# boardV1-4.net
KiCad netlist of a schematic drawn in EAGLE
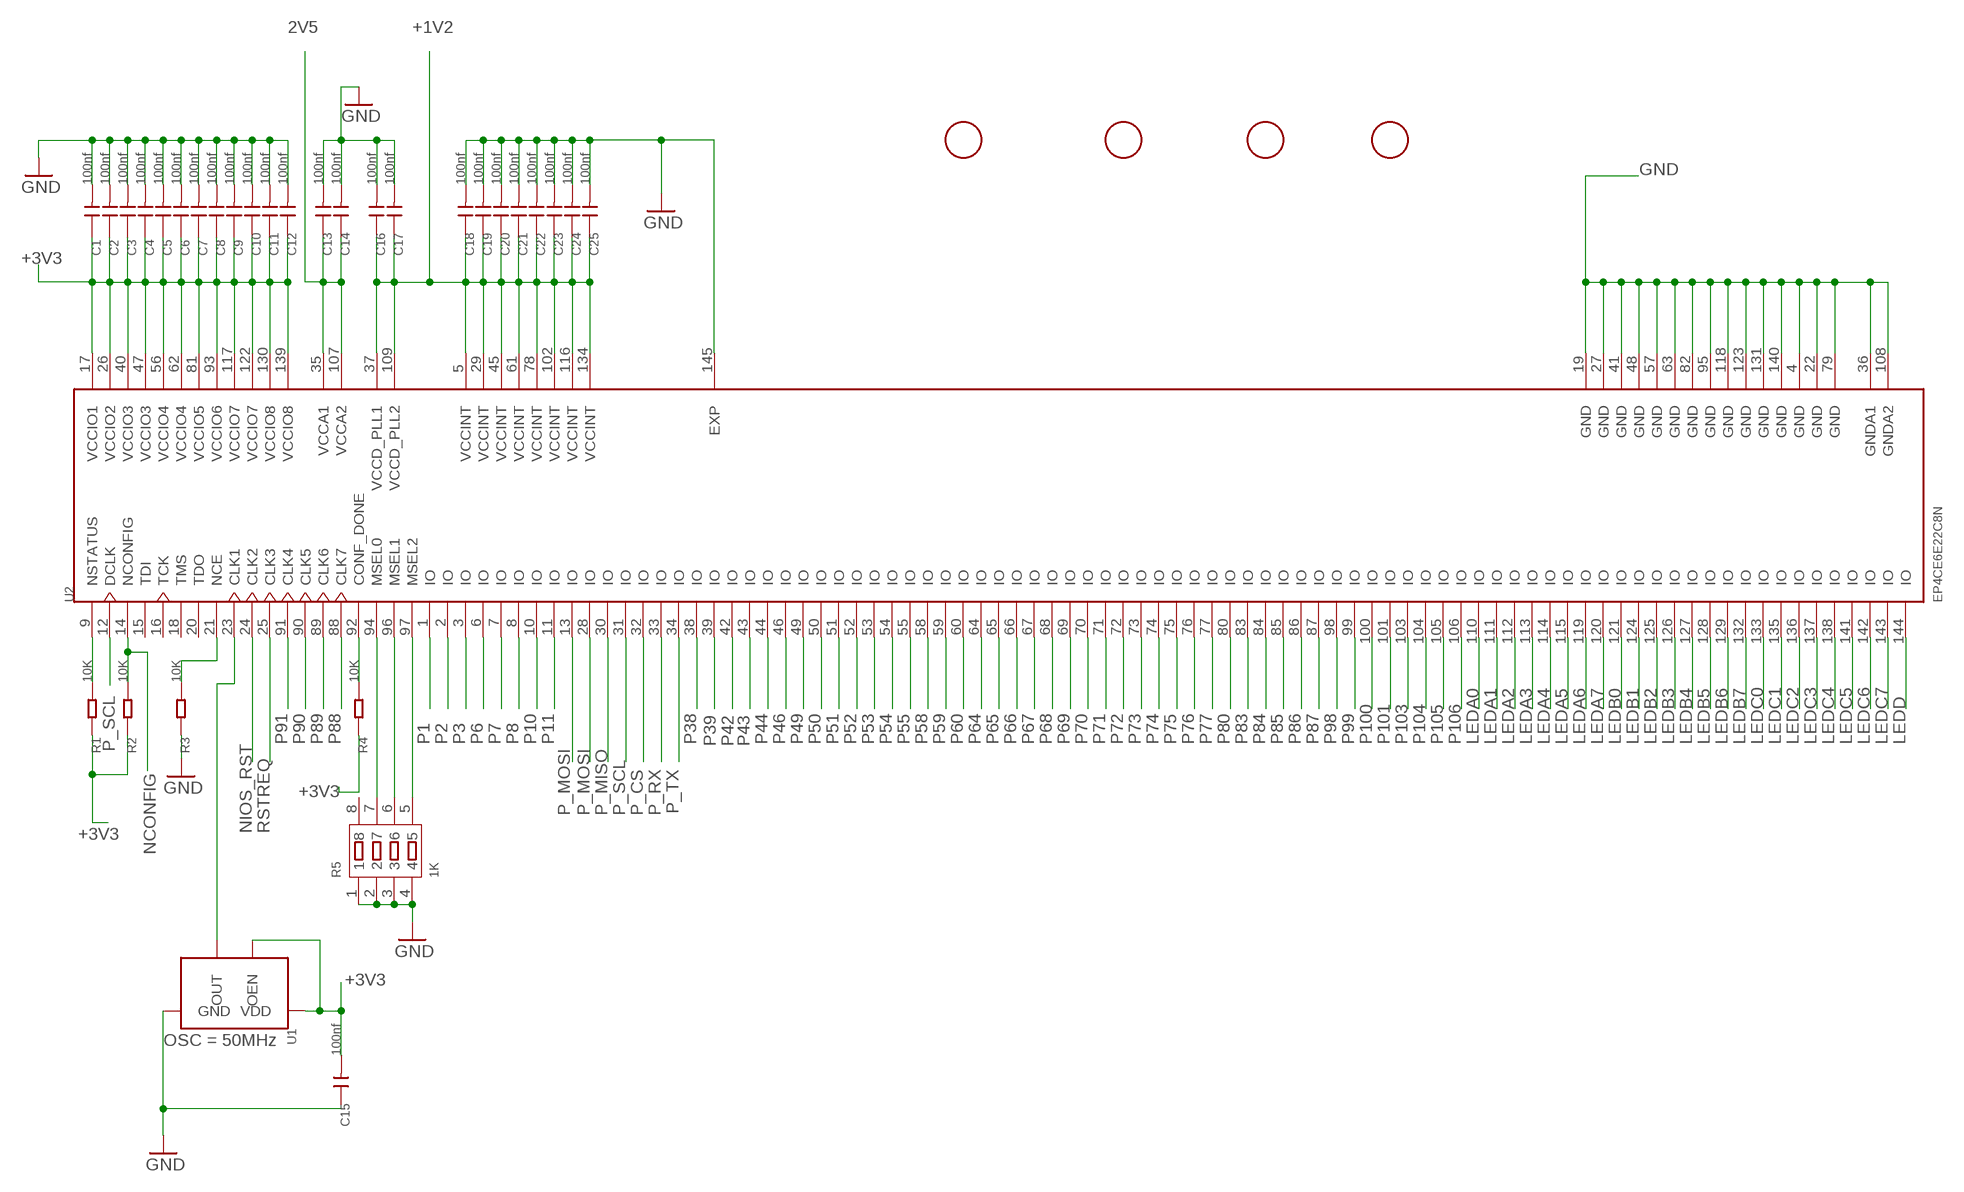
[diagram p0: schematic, sheet 1]
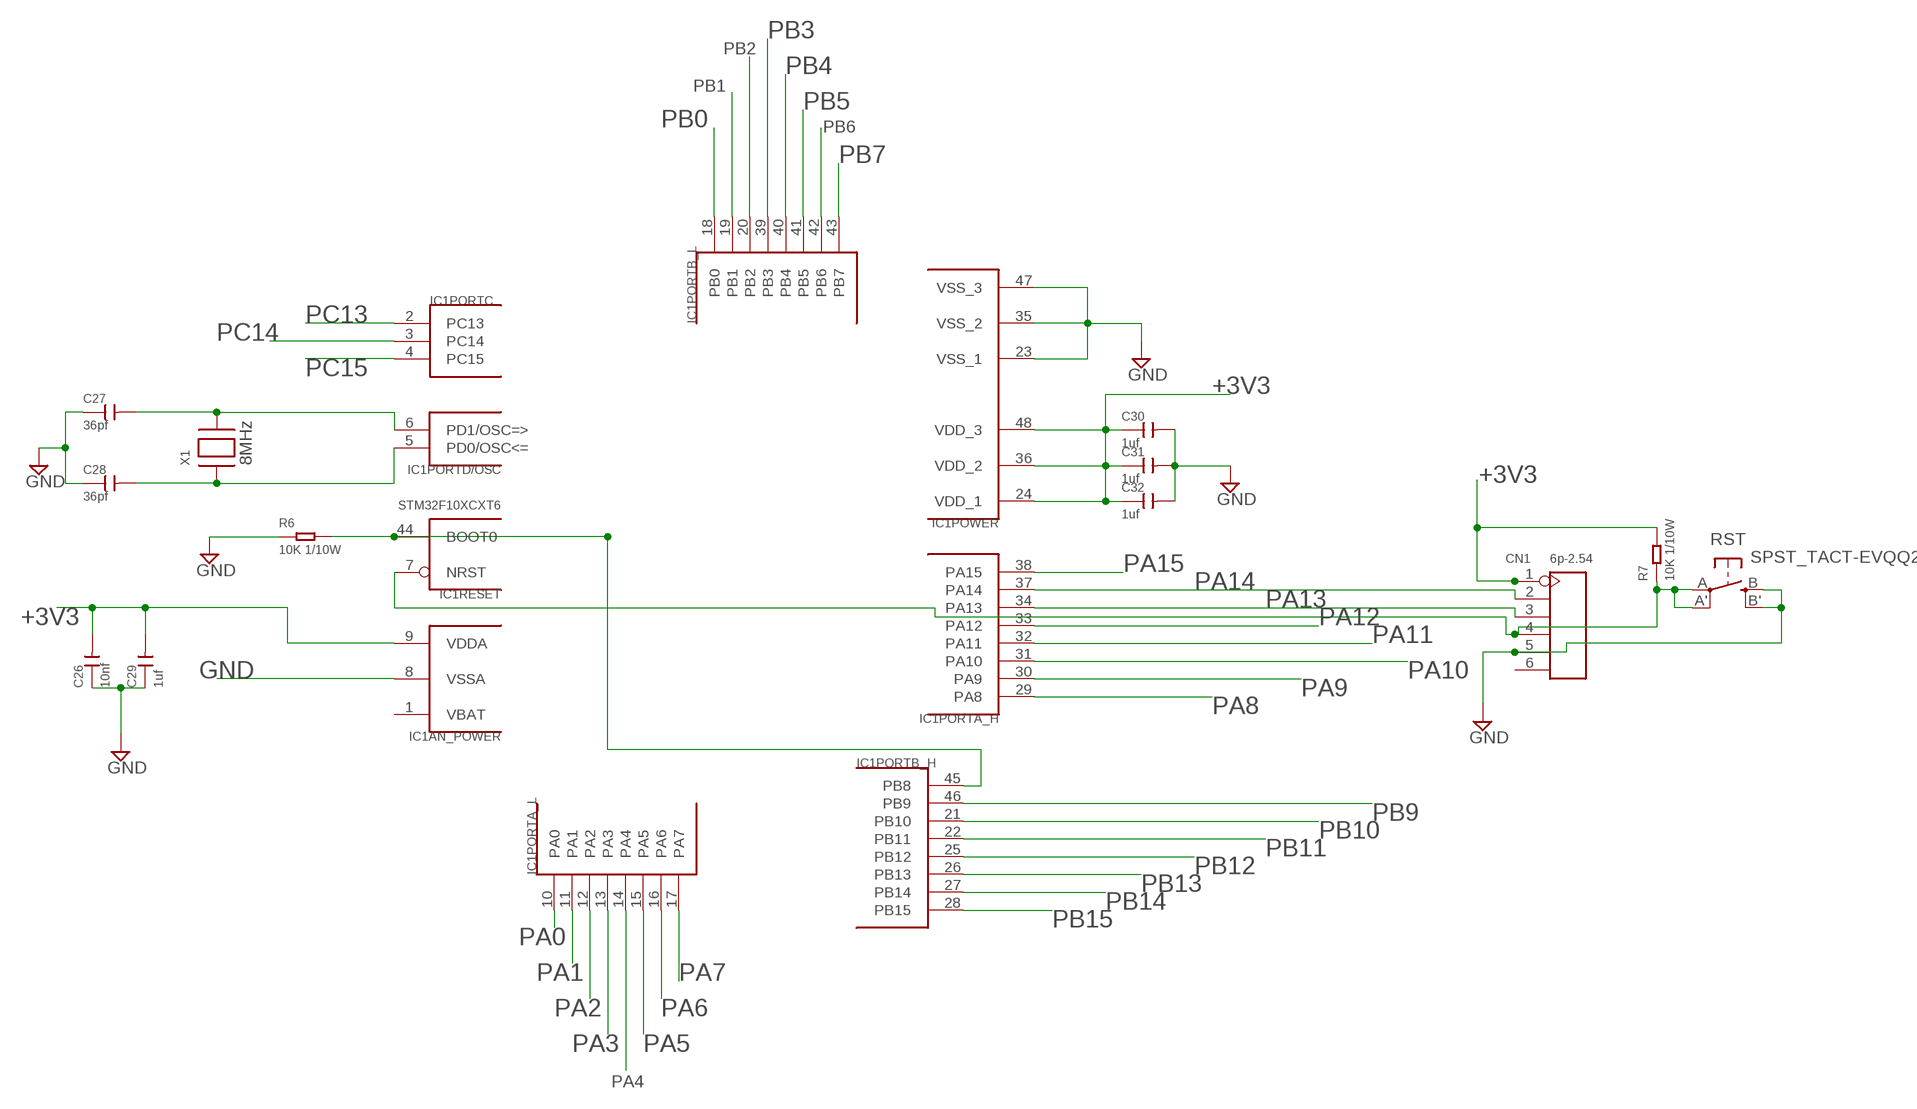
[diagram p1: schematic, sheet 2]
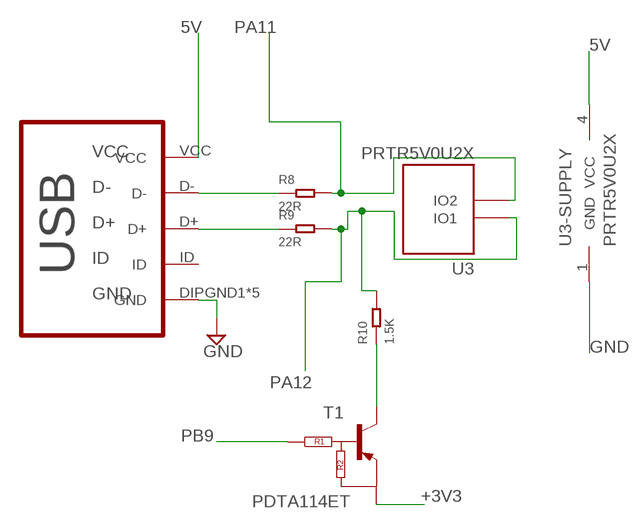
[diagram p2: schematic, sheet 3]
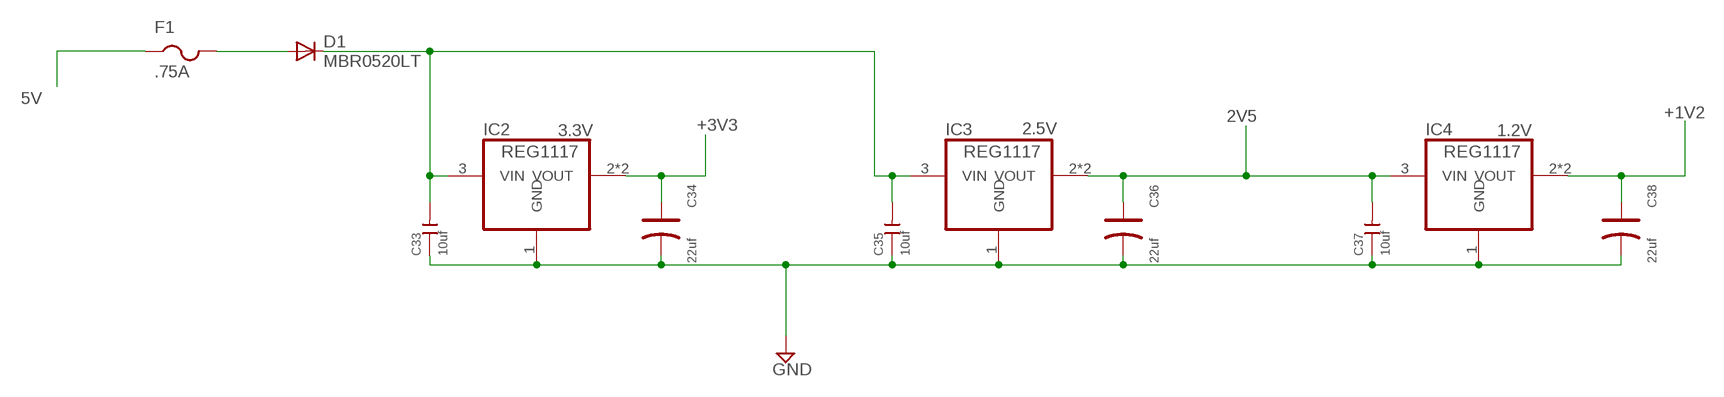
[diagram p3: schematic, sheet 4]
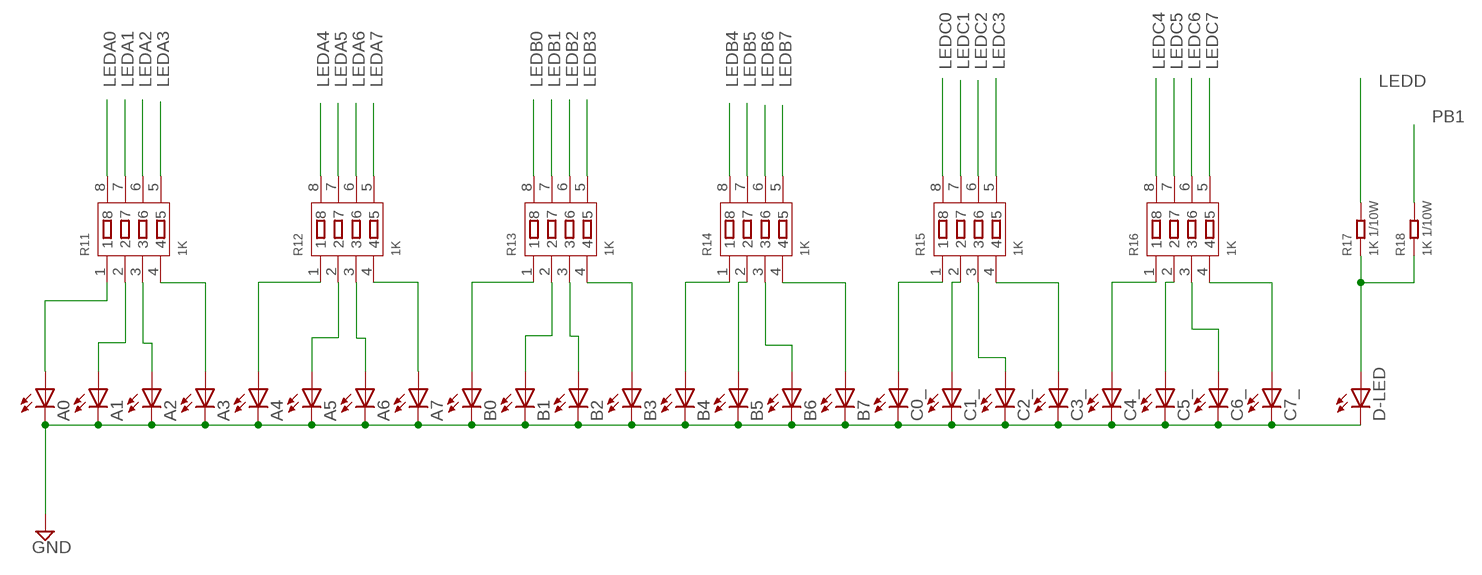
[diagram p4: schematic, sheet 5]
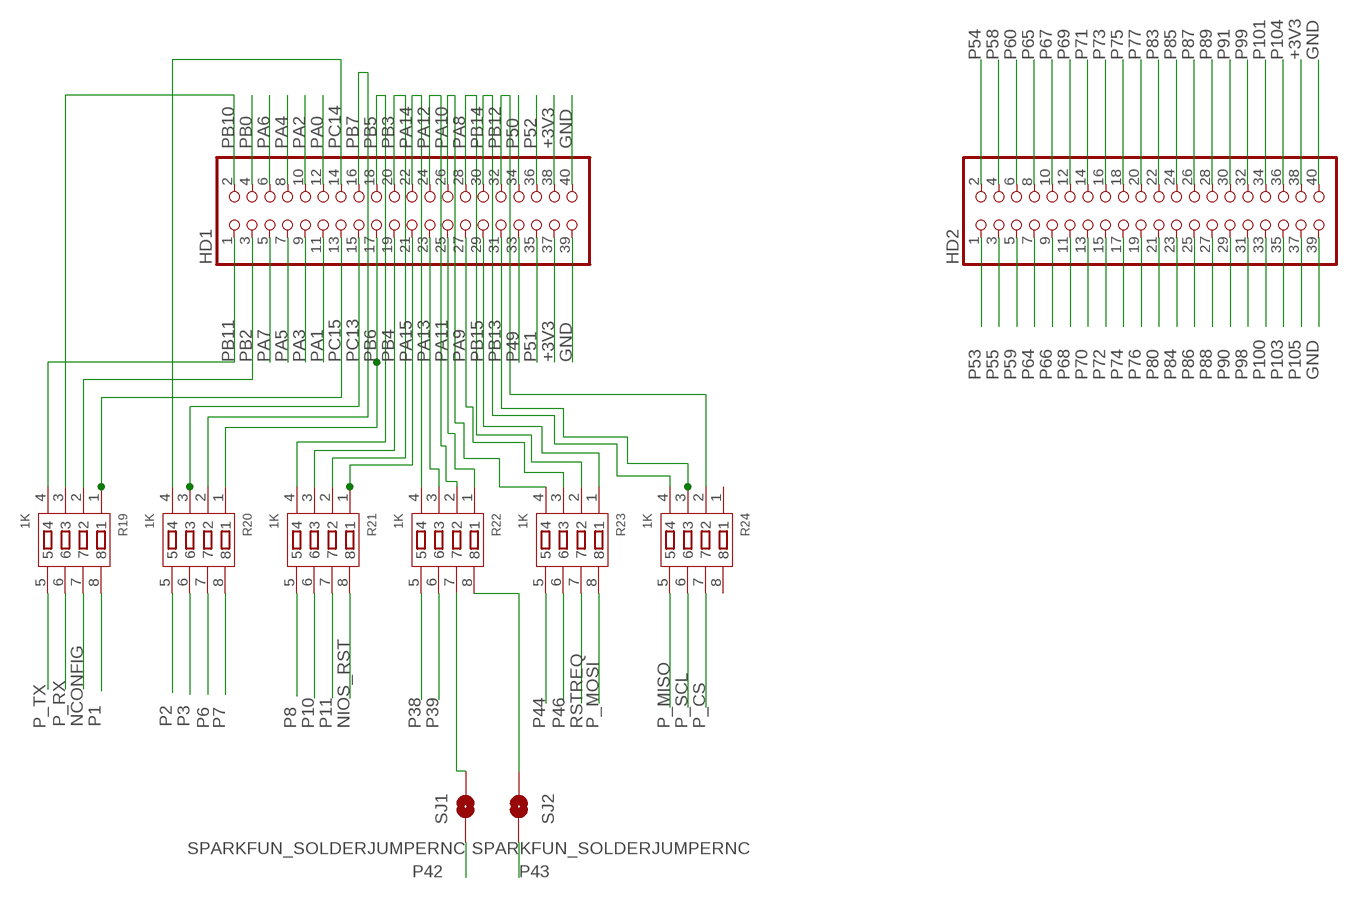
[diagram p5: schematic, sheet 6]
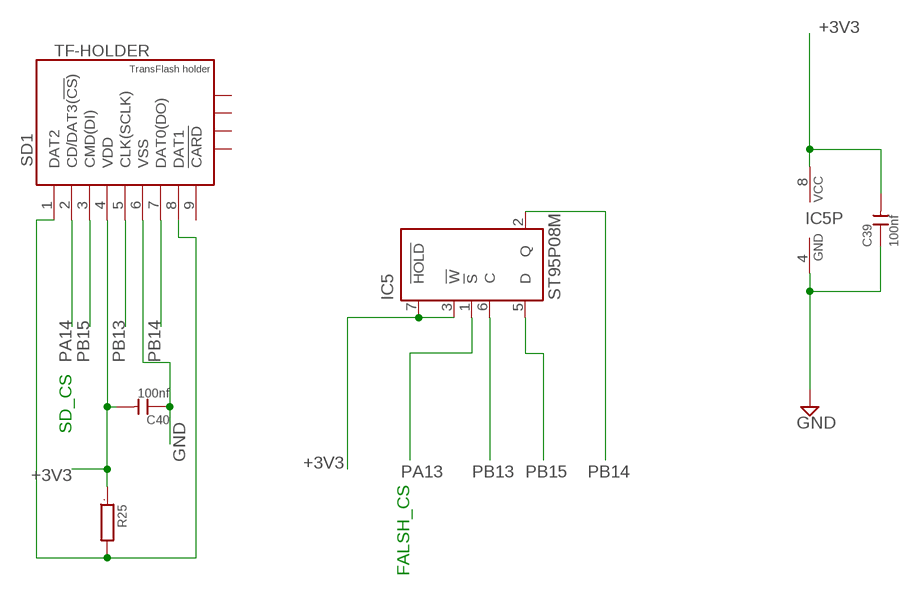
[diagram p6: schematic, sheet 7]

(export (version "E")
  (design (tool "Eeschema 10.0.6"))
  (components
    (comp (ref "HD1")
      (value "PINHD-2X20")
      (footprint "eagle-import:2X20")
      (libsource (lib "eagle-import") (part "PINHD-2X20"))
    )
    (comp (ref "HD2")
      (value "PINHD-2X20")
      (footprint "eagle-import:2X20")
      (libsource (lib "eagle-import") (part "PINHD-2X20"))
    )
    (comp (ref "R19")
      (value "1K")
      (footprint "eagle-import:RA1206-8")
      (fields (field (name "MPN") "Chip-Array-Series-1%"))
      (libsource (lib "eagle-import") (part "Seeed-Resistor_SMD-RES-ARRAY-1K-4R(RA1206-8)"))
    )
    (comp (ref "R20")
      (value "1K")
      (footprint "eagle-import:RA1206-8")
      (fields (field (name "MPN") "Chip-Array-Series-1%"))
      (libsource (lib "eagle-import") (part "Seeed-Resistor_SMD-RES-ARRAY-1K-4R(RA1206-8)"))
    )
    (comp (ref "R21")
      (value "1K")
      (footprint "eagle-import:RA1206-8")
      (fields (field (name "MPN") "Chip-Array-Series-1%"))
      (libsource (lib "eagle-import") (part "Seeed-Resistor_SMD-RES-ARRAY-1K-4R(RA1206-8)"))
    )
    (comp (ref "R22")
      (value "1K")
      (footprint "eagle-import:RA1206-8")
      (fields (field (name "MPN") "Chip-Array-Series-1%"))
      (libsource (lib "eagle-import") (part "Seeed-Resistor_SMD-RES-ARRAY-1K-4R(RA1206-8)"))
    )
    (comp (ref "R23")
      (value "1K")
      (footprint "eagle-import:RA1206-8")
      (fields (field (name "MPN") "Chip-Array-Series-1%"))
      (libsource (lib "eagle-import") (part "Seeed-Resistor_SMD-RES-ARRAY-1K-4R(RA1206-8)"))
    )
    (comp (ref "R24")
      (value "1K")
      (footprint "eagle-import:RA1206-8")
      (fields (field (name "MPN") "Chip-Array-Series-1%"))
      (libsource (lib "eagle-import") (part "Seeed-Resistor_SMD-RES-ARRAY-1K-4R(RA1206-8)"))
    )
    (comp (ref "SJ1")
      (value "SPARKFUN_SOLDERJUMPERNC")
      (footprint "eagle-import:SPARKFUN_SJ_2S")
      (libsource (lib "eagle-import") (part "SPARKFUN_SOLDERJUMPERNC"))
    )
    (comp (ref "SJ2")
      (value "SPARKFUN_SOLDERJUMPERNC")
      (footprint "eagle-import:SPARKFUN_SJ_2S")
      (libsource (lib "eagle-import") (part "SPARKFUN_SOLDERJUMPERNC"))
    )
    (comp (ref "C39")
      (value "100nf")
      (footprint "eagle-import:C0603")
      (fields (field (name "MPN") "CC0603KRX7R9BB104"))
      (libsource (lib "eagle-import") (part "CERAMIC-100NF-50V-10%-X7R(0603)"))
    )
    (comp (ref "C40")
      (value "100nf")
      (footprint "eagle-import:C0603")
      (fields (field (name "MPN") "CC0603KRX7R9BB104"))
      (libsource (lib "eagle-import") (part "CERAMIC-100NF-50V-10%-X7R(0603)"))
    )
    (comp (ref "IC5")
      (value "ST95P08M")
      (footprint "eagle-import:SO08")
      (libsource (lib "eagle-import") (part "ST95P08M"))
    )
    (comp (ref "R25")
      (value "R0603")
      (footprint "eagle-import:0603$1")
      (libsource (lib "eagle-import") (part "R0603"))
    )
    (comp (ref "SD1")
      (value "TF-HOLDER")
      (footprint "eagle-import:TF-PULL")
      (libsource (lib "eagle-import") (part "TF-HOLDER"))
    )
    (comp (ref "C1")
      (value "100nf")
      (footprint "eagle-import:C0603")
      (fields (field (name "MPN") "CC0603KRX7R9BB104"))
      (libsource (lib "eagle-import") (part "Seeed-OPL-Capacitor_CERAMIC-100NF-50V-10%-X7R(0603)"))
    )
    (comp (ref "C2")
      (value "100nf")
      (footprint "eagle-import:C0603")
      (fields (field (name "MPN") "CC0603KRX7R9BB104"))
      (libsource (lib "eagle-import") (part "Seeed-OPL-Capacitor_CERAMIC-100NF-50V-10%-X7R(0603)"))
    )
    (comp (ref "C3")
      (value "100nf")
      (footprint "eagle-import:C0603")
      (fields (field (name "MPN") "CC0603KRX7R9BB104"))
      (libsource (lib "eagle-import") (part "Seeed-OPL-Capacitor_CERAMIC-100NF-50V-10%-X7R(0603)"))
    )
    (comp (ref "C4")
      (value "100nf")
      (footprint "eagle-import:C0603")
      (fields (field (name "MPN") "CC0603KRX7R9BB104"))
      (libsource (lib "eagle-import") (part "Seeed-OPL-Capacitor_CERAMIC-100NF-50V-10%-X7R(0603)"))
    )
    (comp (ref "C5")
      (value "100nf")
      (footprint "eagle-import:C0603")
      (fields (field (name "MPN") "CC0603KRX7R9BB104"))
      (libsource (lib "eagle-import") (part "Seeed-OPL-Capacitor_CERAMIC-100NF-50V-10%-X7R(0603)"))
    )
    (comp (ref "C6")
      (value "100nf")
      (footprint "eagle-import:C0603")
      (fields (field (name "MPN") "CC0603KRX7R9BB104"))
      (libsource (lib "eagle-import") (part "Seeed-OPL-Capacitor_CERAMIC-100NF-50V-10%-X7R(0603)"))
    )
    (comp (ref "C7")
      (value "100nf")
      (footprint "eagle-import:C0603")
      (fields (field (name "MPN") "CC0603KRX7R9BB104"))
      (libsource (lib "eagle-import") (part "Seeed-OPL-Capacitor_CERAMIC-100NF-50V-10%-X7R(0603)"))
    )
    (comp (ref "C8")
      (value "100nf")
      (footprint "eagle-import:C0603")
      (fields (field (name "MPN") "CC0603KRX7R9BB104"))
      (libsource (lib "eagle-import") (part "Seeed-OPL-Capacitor_CERAMIC-100NF-50V-10%-X7R(0603)"))
    )
    (comp (ref "C9")
      (value "100nf")
      (footprint "eagle-import:C0603")
      (fields (field (name "MPN") "CC0603KRX7R9BB104"))
      (libsource (lib "eagle-import") (part "Seeed-OPL-Capacitor_CERAMIC-100NF-50V-10%-X7R(0603)"))
    )
    (comp (ref "C10")
      (value "100nf")
      (footprint "eagle-import:C0603")
      (fields (field (name "MPN") "CC0603KRX7R9BB104"))
      (libsource (lib "eagle-import") (part "Seeed-OPL-Capacitor_CERAMIC-100NF-50V-10%-X7R(0603)"))
    )
    (comp (ref "C11")
      (value "100nf")
      (footprint "eagle-import:C0603")
      (fields (field (name "MPN") "CC0603KRX7R9BB104"))
      (libsource (lib "eagle-import") (part "Seeed-OPL-Capacitor_CERAMIC-100NF-50V-10%-X7R(0603)"))
    )
    (comp (ref "C12")
      (value "100nf")
      (footprint "eagle-import:C0603")
      (fields (field (name "MPN") "CC0603KRX7R9BB104"))
      (libsource (lib "eagle-import") (part "Seeed-OPL-Capacitor_CERAMIC-100NF-50V-10%-X7R(0603)"))
    )
    (comp (ref "C13")
      (value "100nf")
      (footprint "eagle-import:C0603")
      (fields (field (name "MPN") "CC0603KRX7R9BB104"))
      (libsource (lib "eagle-import") (part "Seeed-OPL-Capacitor_CERAMIC-100NF-50V-10%-X7R(0603)"))
    )
    (comp (ref "C14")
      (value "100nf")
      (footprint "eagle-import:C0603")
      (fields (field (name "MPN") "CC0603KRX7R9BB104"))
      (libsource (lib "eagle-import") (part "Seeed-OPL-Capacitor_CERAMIC-100NF-50V-10%-X7R(0603)"))
    )
    (comp (ref "C15")
      (value "100nf")
      (footprint "eagle-import:C0603")
      (fields (field (name "MPN") "CC0603KRX7R9BB104"))
      (libsource (lib "eagle-import") (part "Seeed-OPL-Capacitor_CERAMIC-100NF-50V-10%-X7R(0603)"))
    )
    (comp (ref "C16")
      (value "100nf")
      (footprint "eagle-import:C0603")
      (fields (field (name "MPN") "CC0603KRX7R9BB104"))
      (libsource (lib "eagle-import") (part "Seeed-OPL-Capacitor_CERAMIC-100NF-50V-10%-X7R(0603)"))
    )
    (comp (ref "C17")
      (value "100nf")
      (footprint "eagle-import:C0603")
      (fields (field (name "MPN") "CC0603KRX7R9BB104"))
      (libsource (lib "eagle-import") (part "Seeed-OPL-Capacitor_CERAMIC-100NF-50V-10%-X7R(0603)"))
    )
    (comp (ref "C18")
      (value "100nf")
      (footprint "eagle-import:C0603")
      (fields (field (name "MPN") "CC0603KRX7R9BB104"))
      (libsource (lib "eagle-import") (part "Seeed-OPL-Capacitor_CERAMIC-100NF-50V-10%-X7R(0603)"))
    )
    (comp (ref "C19")
      (value "100nf")
      (footprint "eagle-import:C0603")
      (fields (field (name "MPN") "CC0603KRX7R9BB104"))
      (libsource (lib "eagle-import") (part "Seeed-OPL-Capacitor_CERAMIC-100NF-50V-10%-X7R(0603)"))
    )
    (comp (ref "C20")
      (value "100nf")
      (footprint "eagle-import:C0603")
      (fields (field (name "MPN") "CC0603KRX7R9BB104"))
      (libsource (lib "eagle-import") (part "Seeed-OPL-Capacitor_CERAMIC-100NF-50V-10%-X7R(0603)"))
    )
    (comp (ref "C21")
      (value "100nf")
      (footprint "eagle-import:C0603")
      (fields (field (name "MPN") "CC0603KRX7R9BB104"))
      (libsource (lib "eagle-import") (part "Seeed-OPL-Capacitor_CERAMIC-100NF-50V-10%-X7R(0603)"))
    )
    (comp (ref "C22")
      (value "100nf")
      (footprint "eagle-import:C0603")
      (fields (field (name "MPN") "CC0603KRX7R9BB104"))
      (libsource (lib "eagle-import") (part "Seeed-OPL-Capacitor_CERAMIC-100NF-50V-10%-X7R(0603)"))
    )
    (comp (ref "C23")
      (value "100nf")
      (footprint "eagle-import:C0603")
      (fields (field (name "MPN") "CC0603KRX7R9BB104"))
      (libsource (lib "eagle-import") (part "Seeed-OPL-Capacitor_CERAMIC-100NF-50V-10%-X7R(0603)"))
    )
    (comp (ref "C24")
      (value "100nf")
      (footprint "eagle-import:C0603")
      (fields (field (name "MPN") "CC0603KRX7R9BB104"))
      (libsource (lib "eagle-import") (part "Seeed-OPL-Capacitor_CERAMIC-100NF-50V-10%-X7R(0603)"))
    )
    (comp (ref "C25")
      (value "100nf")
      (footprint "eagle-import:C0603")
      (fields (field (name "MPN") "CC0603KRX7R9BB104"))
      (libsource (lib "eagle-import") (part "Seeed-OPL-Capacitor_CERAMIC-100NF-50V-10%-X7R(0603)"))
    )
    (comp (ref "R1")
      (value "10K")
      (footprint "eagle-import:R0603")
      (fields (field (name "MPN") "RC0603FR-0710KL"))
      (libsource (lib "eagle-import") (part "SMD-RES-10K-1%-1/10W(0603)"))
    )
    (comp (ref "R2")
      (value "10K")
      (footprint "eagle-import:R0603")
      (fields (field (name "MPN") "RC0603FR-0710KL"))
      (libsource (lib "eagle-import") (part "SMD-RES-10K-1%-1/10W(0603)"))
    )
    (comp (ref "R3")
      (value "10K")
      (footprint "eagle-import:R0603")
      (fields (field (name "MPN") "RC0603FR-0710KL"))
      (libsource (lib "eagle-import") (part "SMD-RES-10K-1%-1/10W(0603)"))
    )
    (comp (ref "R4")
      (value "10K")
      (footprint "eagle-import:R0603")
      (fields (field (name "MPN") "RC0603FR-0710KL"))
      (libsource (lib "eagle-import") (part "SMD-RES-10K-1%-1/10W(0603)"))
    )
    (comp (ref "R5")
      (value "1K")
      (footprint "eagle-import:RA1206-8")
      (fields (field (name "MPN") "Chip-Array-Series-1%"))
      (libsource (lib "eagle-import") (part "SMD-RES-ARRAY-1K-4R(RA1206-8)"))
    )
    (comp (ref "U$1")
      (value "FIDUCIAL")
      (footprint "eagle-import:FIDUCIAL_1MM")
      (libsource (lib "eagle-import") (part "FIDUCIAL"))
    )
    (comp (ref "U$2")
      (value "FIDUCIAL")
      (footprint "eagle-import:FIDUCIAL_1MM")
      (libsource (lib "eagle-import") (part "FIDUCIAL"))
    )
    (comp (ref "U$3")
      (value "FIDUCIAL")
      (footprint "eagle-import:FIDUCIAL_1MM")
      (libsource (lib "eagle-import") (part "FIDUCIAL"))
    )
    (comp (ref "U$4")
      (value "FIDUCIAL")
      (footprint "eagle-import:FIDUCIAL_1MM")
      (libsource (lib "eagle-import") (part "FIDUCIAL"))
    )
    (comp (ref "U1")
      (value "306020041_OSC_32.768KHZ-3225_4P")
      (footprint "eagle-import:X3225_4P")
      (fields (field (name "OSC") "50MHz"))
      (libsource (lib "eagle-import") (part "306020041_OSC_32.768KHZ-3225_4P"))
    )
    (comp (ref "U2")
      (value "EP4CE6E22C8N")
      (footprint "eagle-import:QFP50P2200X2200X165-145N")
      (fields (field (name "MF") "Altera"))
      (libsource (lib "eagle-import") (part "EP4CE6E22C8N"))
    )
    (comp (ref "A0")
      (value "LEDCHIPLED_0603")
      (footprint "eagle-import:CHIPLED_0603")
      (libsource (lib "eagle-import") (part "LEDCHIPLED_0603"))
    )
    (comp (ref "A1")
      (value "LEDCHIPLED_0603")
      (footprint "eagle-import:CHIPLED_0603")
      (libsource (lib "eagle-import") (part "LEDCHIPLED_0603"))
    )
    (comp (ref "A2")
      (value "LEDCHIPLED_0603")
      (footprint "eagle-import:CHIPLED_0603")
      (libsource (lib "eagle-import") (part "LEDCHIPLED_0603"))
    )
    (comp (ref "A3")
      (value "LEDCHIPLED_0603")
      (footprint "eagle-import:CHIPLED_0603")
      (libsource (lib "eagle-import") (part "LEDCHIPLED_0603"))
    )
    (comp (ref "A4")
      (value "LEDCHIPLED_0603")
      (footprint "eagle-import:CHIPLED_0603")
      (libsource (lib "eagle-import") (part "LEDCHIPLED_0603"))
    )
    (comp (ref "A5")
      (value "LEDCHIPLED_0603")
      (footprint "eagle-import:CHIPLED_0603")
      (libsource (lib "eagle-import") (part "LEDCHIPLED_0603"))
    )
    (comp (ref "A6")
      (value "LEDCHIPLED_0603")
      (footprint "eagle-import:CHIPLED_0603")
      (libsource (lib "eagle-import") (part "LEDCHIPLED_0603"))
    )
    (comp (ref "A7")
      (value "LEDCHIPLED_0603")
      (footprint "eagle-import:CHIPLED_0603")
      (libsource (lib "eagle-import") (part "LEDCHIPLED_0603"))
    )
    (comp (ref "B0")
      (value "LEDCHIPLED_0603")
      (footprint "eagle-import:CHIPLED_0603")
      (libsource (lib "eagle-import") (part "LEDCHIPLED_0603"))
    )
    (comp (ref "B1")
      (value "LEDCHIPLED_0603")
      (footprint "eagle-import:CHIPLED_0603")
      (libsource (lib "eagle-import") (part "LEDCHIPLED_0603"))
    )
    (comp (ref "B2")
      (value "LEDCHIPLED_0603")
      (footprint "eagle-import:CHIPLED_0603")
      (libsource (lib "eagle-import") (part "LEDCHIPLED_0603"))
    )
    (comp (ref "B3")
      (value "LEDCHIPLED_0603")
      (footprint "eagle-import:CHIPLED_0603")
      (libsource (lib "eagle-import") (part "LEDCHIPLED_0603"))
    )
    (comp (ref "B4")
      (value "LEDCHIPLED_0603")
      (footprint "eagle-import:CHIPLED_0603")
      (libsource (lib "eagle-import") (part "LEDCHIPLED_0603"))
    )
    (comp (ref "B5")
      (value "LEDCHIPLED_0603")
      (footprint "eagle-import:CHIPLED_0603")
      (libsource (lib "eagle-import") (part "LEDCHIPLED_0603"))
    )
    (comp (ref "B6")
      (value "LEDCHIPLED_0603")
      (footprint "eagle-import:CHIPLED_0603")
      (libsource (lib "eagle-import") (part "LEDCHIPLED_0603"))
    )
    (comp (ref "B7")
      (value "LEDCHIPLED_0603")
      (footprint "eagle-import:CHIPLED_0603")
      (libsource (lib "eagle-import") (part "LEDCHIPLED_0603"))
    )
    (comp (ref "C0_")
      (value "LEDCHIPLED_0603")
      (footprint "eagle-import:CHIPLED_0603")
      (libsource (lib "eagle-import") (part "LEDCHIPLED_0603"))
    )
    (comp (ref "C1_")
      (value "LEDCHIPLED_0603")
      (footprint "eagle-import:CHIPLED_0603")
      (libsource (lib "eagle-import") (part "LEDCHIPLED_0603"))
    )
    (comp (ref "C2_")
      (value "LEDCHIPLED_0603")
      (footprint "eagle-import:CHIPLED_0603")
      (libsource (lib "eagle-import") (part "LEDCHIPLED_0603"))
    )
    (comp (ref "C3_")
      (value "LEDCHIPLED_0603")
      (footprint "eagle-import:CHIPLED_0603")
      (libsource (lib "eagle-import") (part "LEDCHIPLED_0603"))
    )
    (comp (ref "C4_")
      (value "LEDCHIPLED_0603")
      (footprint "eagle-import:CHIPLED_0603")
      (libsource (lib "eagle-import") (part "LEDCHIPLED_0603"))
    )
    (comp (ref "C5_")
      (value "LEDCHIPLED_0603")
      (footprint "eagle-import:CHIPLED_0603")
      (libsource (lib "eagle-import") (part "LEDCHIPLED_0603"))
    )
    (comp (ref "C6_")
      (value "LEDCHIPLED_0603")
      (footprint "eagle-import:CHIPLED_0603")
      (libsource (lib "eagle-import") (part "LEDCHIPLED_0603"))
    )
    (comp (ref "C7_")
      (value "LEDCHIPLED_0603")
      (footprint "eagle-import:CHIPLED_0603")
      (libsource (lib "eagle-import") (part "LEDCHIPLED_0603"))
    )
    (comp (ref "D-LED")
      (value "LEDCHIPLED_0603")
      (footprint "eagle-import:CHIPLED_0603")
      (libsource (lib "eagle-import") (part "LEDCHIPLED_0603"))
    )
    (comp (ref "R11")
      (value "1K")
      (footprint "eagle-import:RA1206-8")
      (fields (field (name "MPN") "Chip-Array-Series-1%"))
      (libsource (lib "eagle-import") (part "SMD-RES-ARRAY-1K-4R(RA1206-8)"))
    )
    (comp (ref "R12")
      (value "1K")
      (footprint "eagle-import:RA1206-8")
      (fields (field (name "MPN") "Chip-Array-Series-1%"))
      (libsource (lib "eagle-import") (part "SMD-RES-ARRAY-1K-4R(RA1206-8)"))
    )
    (comp (ref "R13")
      (value "1K")
      (footprint "eagle-import:RA1206-8")
      (fields (field (name "MPN") "Chip-Array-Series-1%"))
      (libsource (lib "eagle-import") (part "SMD-RES-ARRAY-1K-4R(RA1206-8)"))
    )
    (comp (ref "R14")
      (value "1K")
      (footprint "eagle-import:RA1206-8")
      (fields (field (name "MPN") "Chip-Array-Series-1%"))
      (libsource (lib "eagle-import") (part "SMD-RES-ARRAY-1K-4R(RA1206-8)"))
    )
    (comp (ref "R15")
      (value "1K")
      (footprint "eagle-import:RA1206-8")
      (fields (field (name "MPN") "Chip-Array-Series-1%"))
      (libsource (lib "eagle-import") (part "SMD-RES-ARRAY-1K-4R(RA1206-8)"))
    )
    (comp (ref "R16")
      (value "1K")
      (footprint "eagle-import:RA1206-8")
      (fields (field (name "MPN") "Chip-Array-Series-1%"))
      (libsource (lib "eagle-import") (part "SMD-RES-ARRAY-1K-4R(RA1206-8)"))
    )
    (comp (ref "R17")
      (value "1K 1/10W")
      (footprint "eagle-import:R0603")
      (fields (field (name "MPN") "RC0603JR-071KL"))
      (libsource (lib "eagle-import") (part "SMD-RES-1K-5%-1/10W(0603)"))
    )
    (comp (ref "R18")
      (value "1K 1/10W")
      (footprint "eagle-import:R0603")
      (fields (field (name "MPN") "RC0603JR-071KL"))
      (libsource (lib "eagle-import") (part "SMD-RES-1K-5%-1/10W(0603)"))
    )
    (comp (ref "C33")
      (value "10uf")
      (footprint "eagle-import:C0805")
      (fields (field (name "MPN") "CC0805KKX5R8BB106"))
      (libsource (lib "eagle-import") (part "CERAMIC-10UF-25V-10%-X5R(0805)"))
    )
    (comp (ref "C34")
      (value "22uf")
      (footprint "eagle-import:AVX-A")
      (fields (field (name "MPN") "TAJA226K006RNJ"))
      (libsource (lib "eagle-import") (part "TANTALUM-SMD-22UF-6.3V(AVX-A)"))
    )
    (comp (ref "C35")
      (value "10uf")
      (footprint "eagle-import:C0805")
      (fields (field (name "MPN") "CC0805KKX5R8BB106"))
      (libsource (lib "eagle-import") (part "CERAMIC-10UF-25V-10%-X5R(0805)"))
    )
    (comp (ref "C36")
      (value "22uf")
      (footprint "eagle-import:AVX-A")
      (fields (field (name "MPN") "TAJA226K006RNJ"))
      (libsource (lib "eagle-import") (part "TANTALUM-SMD-22UF-6.3V(AVX-A)"))
    )
    (comp (ref "C37")
      (value "10uf")
      (footprint "eagle-import:C0805")
      (fields (field (name "MPN") "CC0805KKX5R8BB106"))
      (libsource (lib "eagle-import") (part "CERAMIC-10UF-25V-10%-X5R(0805)"))
    )
    (comp (ref "C38")
      (value "22uf")
      (footprint "eagle-import:AVX-A")
      (fields (field (name "MPN") "TAJA226K006RNJ"))
      (libsource (lib "eagle-import") (part "TANTALUM-SMD-22UF-6.3V(AVX-A)"))
    )
    (comp (ref "D1")
      (value "MBR0520LT")
      (footprint "eagle-import:SOD123")
      (libsource (lib "eagle-import") (part "MBR0520LT"))
    )
    (comp (ref "F1")
      (value ".75A")
      (footprint "eagle-import:R1206")
      (libsource (lib "eagle-import") (part "PTCFUSE-1206"))
    )
    (comp (ref "IC2")
      (value "REG1117")
      (footprint "eagle-import:SOT223")
      (fields (field (name "OUT") "3.3V"))
      (libsource (lib "eagle-import") (part "REG1117"))
    )
    (comp (ref "IC3")
      (value "REG1117")
      (footprint "eagle-import:SOT223")
      (fields (field (name "OUT") "2.5V"))
      (libsource (lib "eagle-import") (part "REG1117"))
    )
    (comp (ref "IC4")
      (value "REG1117")
      (footprint "eagle-import:SOT223")
      (fields (field (name "V") "1.2V"))
      (libsource (lib "eagle-import") (part "REG1117"))
    )
    (comp (ref "C26")
      (value "10nf")
      (footprint "eagle-import:C0603")
      (fields (field (name "MPN") "CC0603KRX7R9BB103"))
      (libsource (lib "eagle-import") (part "CERAMIC-10NF-50V-10%-X7R(0603)"))
    )
    (comp (ref "C27")
      (value "36pf")
      (footprint "eagle-import:C0603")
      (fields (field (name "MPN") "CC0603JRNPO9BN120"))
      (libsource (lib "eagle-import") (part "CERAMIC-12PF-50V-5%-NPO(0603)"))
    )
    (comp (ref "C28")
      (value "36pf")
      (footprint "eagle-import:C0603")
      (fields (field (name "MPN") "CC0603JRNPO9BN120"))
      (libsource (lib "eagle-import") (part "CERAMIC-12PF-50V-5%-NPO(0603)"))
    )
    (comp (ref "C29")
      (value "1uf")
      (footprint "eagle-import:C0603")
      (fields (field (name "MPN") "CC0603KRX7R8BB105"))
      (libsource (lib "eagle-import") (part "CERAMIC-1UF-25V-10%-X7R(0603)"))
    )
    (comp (ref "C30")
      (value "1uf")
      (footprint "eagle-import:C0603")
      (fields (field (name "MPN") "CC0603KRX7R8BB105"))
      (libsource (lib "eagle-import") (part "CERAMIC-1UF-25V-10%-X7R(0603)"))
    )
    (comp (ref "C31")
      (value "1uf")
      (footprint "eagle-import:C0603")
      (fields (field (name "MPN") "CC0603KRX7R8BB105"))
      (libsource (lib "eagle-import") (part "CERAMIC-1UF-25V-10%-X7R(0603)"))
    )
    (comp (ref "C32")
      (value "1uf")
      (footprint "eagle-import:C0603")
      (fields (field (name "MPN") "CC0603KRX7R8BB105"))
      (libsource (lib "eagle-import") (part "CERAMIC-1UF-25V-10%-X7R(0603)"))
    )
    (comp (ref "CN1")
      (value "6p-2.54")
      (footprint "eagle-import:H6-2.54")
      (fields (field (name "MPN") "F185-1106A1BSYC1"))
      (libsource (lib "eagle-import") (part "DIP-BLACK-FEMALE-HEADER-VERT(6P-2.54)"))
    )
    (comp (ref "IC1")
      (value "STM32F10XCXT6")
      (footprint "eagle-import:TQFP48")
      (libsource (lib "eagle-import") (part "STM32F10XCXT6"))
    )
    (comp (ref "R6")
      (value "10K 1/10W")
      (footprint "eagle-import:R0603")
      (fields (field (name "MPN") "RC0603JR-0710KL"))
      (libsource (lib "eagle-import") (part "SMD-RES-10K-5%-1/10W(0603)"))
    )
    (comp (ref "R7")
      (value "10K 1/10W")
      (footprint "eagle-import:R0603")
      (fields (field (name "MPN") "RC0603JR-0710KL"))
      (libsource (lib "eagle-import") (part "SMD-RES-10K-5%-1/10W(0603)"))
    )
    (comp (ref "RST")
      (value "SPST_TACT-EVQQ2")
      (footprint "eagle-import:EVQ-Q2")
      (libsource (lib "eagle-import") (part "SPST_TACT-EVQQ2"))
    )
    (comp (ref "X1")
      (value "306010047_XTAL_12MHZ-5032_2P")
      (footprint "eagle-import:X5032_2P")
      (fields (field (name "FQ") "8MHz"))
      (libsource (lib "eagle-import") (part "306010047_XTAL_12MHZ-5032_2P"))
    )
    (comp (ref "R8")
      (value "22R")
      (footprint "eagle-import:R0603")
      (fields (field (name "MPN") "RC0603JR-0722RL"))
      (libsource (lib "eagle-import") (part "SMD-RES-22R-5%-1/10W(0603)"))
    )
    (comp (ref "R9")
      (value "22R")
      (footprint "eagle-import:R0603")
      (fields (field (name "MPN") "RC0603JR-0722RL"))
      (libsource (lib "eagle-import") (part "SMD-RES-22R-5%-1/10W(0603)"))
    )
    (comp (ref "R10")
      (value "1.5K")
      (footprint "eagle-import:R0603")
      (fields (field (name "MPN") "RC0603FR-071K5L"))
      (libsource (lib "eagle-import") (part "SMD-RES-1.5K-1%-1/10W(0603)"))
    )
    (comp (ref "T1")
      (value "PDTA114ET")
      (footprint "eagle-import:SOT23")
      (libsource (lib "eagle-import") (part "PDTA114TE"))
    )
    (comp (ref "U3")
      (value "PRTR5V0U2X")
      (footprint "eagle-import:SOT-143B")
      (fields
        (field (name "MANUFACTURER") "NXP Semiconductors")
        (field (name "PART_NUMBER") "PRTR5V0U2X,215")
      )
      (libsource (lib "eagle-import") (part "PRTR5V0U2X?"))
    )
    (comp (ref "USB")
      (value "MICRO-USB-B")
      (footprint "eagle-import:MICRO_USB_4_LEGS")
      (libsource (lib "eagle-import") (part "MICRO-USB-B"))
    )
  )
  (nets
    (net (code "1") (name "+1V2") (class "Default")
      (node (ref "C16") (pin "1") (pinfunction "1_1") (pintype "passive"))
      (node (ref "C17") (pin "1") (pinfunction "1_1") (pintype "passive"))
      (node (ref "C18") (pin "1") (pinfunction "1_1") (pintype "passive"))
      (node (ref "C19") (pin "1") (pinfunction "1_1") (pintype "passive"))
      (node (ref "C20") (pin "1") (pinfunction "1_1") (pintype "passive"))
      (node (ref "C21") (pin "1") (pinfunction "1_1") (pintype "passive"))
      (node (ref "C22") (pin "1") (pinfunction "1_1") (pintype "passive"))
      (node (ref "C23") (pin "1") (pinfunction "1_1") (pintype "passive"))
      (node (ref "C24") (pin "1") (pinfunction "1_1") (pintype "passive"))
      (node (ref "C25") (pin "1") (pinfunction "1_1") (pintype "passive"))
      (node (ref "C38") (pin "+") (pinfunction "+_+") (pintype "passive"))
      (node (ref "IC4") (pin "2") (pinfunction "VOUT_2") (pintype "output"))
      (node (ref "IC4") (pin "4") (pinfunction "VOUT_4") (pintype "output"))
      (node (ref "U2") (pin "102") (pinfunction "VCCINT_102") (pintype "power_in"))
      (node (ref "U2") (pin "109") (pinfunction "VCCD_PLL2_109") (pintype "power_in"))
      (node (ref "U2") (pin "116") (pinfunction "VCCINT_116") (pintype "power_in"))
      (node (ref "U2") (pin "134") (pinfunction "VCCINT_134") (pintype "power_in"))
      (node (ref "U2") (pin "29") (pinfunction "VCCINT_29") (pintype "power_in"))
      (node (ref "U2") (pin "37") (pinfunction "VCCD_PLL1_37") (pintype "power_in"))
      (node (ref "U2") (pin "45") (pinfunction "VCCINT_45") (pintype "power_in"))
      (node (ref "U2") (pin "5") (pinfunction "VCCINT_5") (pintype "power_in"))
      (node (ref "U2") (pin "61") (pinfunction "VCCINT_61") (pintype "power_in"))
      (node (ref "U2") (pin "78") (pinfunction "VCCINT_78") (pintype "power_in"))
    )
    (net (code "2") (name "+3V3") (class "Default")
      (node (ref "C1") (pin "1") (pinfunction "1_1") (pintype "passive"))
      (node (ref "C10") (pin "1") (pinfunction "1_1") (pintype "passive"))
      (node (ref "C11") (pin "1") (pinfunction "1_1") (pintype "passive"))
      (node (ref "C12") (pin "1") (pinfunction "1_1") (pintype "passive"))
      (node (ref "C15") (pin "2") (pinfunction "2_2") (pintype "passive"))
      (node (ref "C2") (pin "1") (pinfunction "1_1") (pintype "passive"))
      (node (ref "C26") (pin "2") (pinfunction "2_2") (pintype "passive"))
      (node (ref "C29") (pin "2") (pinfunction "2_2") (pintype "passive"))
      (node (ref "C3") (pin "1") (pinfunction "1_1") (pintype "passive"))
      (node (ref "C30") (pin "1") (pinfunction "1_1") (pintype "passive"))
      (node (ref "C31") (pin "1") (pinfunction "1_1") (pintype "passive"))
      (node (ref "C32") (pin "1") (pinfunction "1_1") (pintype "passive"))
      (node (ref "C34") (pin "+") (pinfunction "+_+") (pintype "passive"))
      (node (ref "C39") (pin "2") (pinfunction "2_2") (pintype "passive"))
      (node (ref "C4") (pin "1") (pinfunction "1_1") (pintype "passive"))
      (node (ref "C40") (pin "2") (pinfunction "2_2") (pintype "passive"))
      (node (ref "C5") (pin "1") (pinfunction "1_1") (pintype "passive"))
      (node (ref "C6") (pin "1") (pinfunction "1_1") (pintype "passive"))
      (node (ref "C7") (pin "1") (pinfunction "1_1") (pintype "passive"))
      (node (ref "C8") (pin "1") (pinfunction "1_1") (pintype "passive"))
      (node (ref "C9") (pin "1") (pinfunction "1_1") (pintype "passive"))
      (node (ref "CN1") (pin "1") (pinfunction "1_1") (pintype "bidirectional"))
      (node (ref "HD1") (pin "37") (pinfunction "37_37") (pintype "passive"))
      (node (ref "HD1") (pin "38") (pinfunction "38_38") (pintype "passive"))
      (node (ref "HD2") (pin "38") (pinfunction "38_38") (pintype "passive"))
      (node (ref "IC1") (pin "24") (pinfunction "VDD_1_24") (pintype "power_in"))
      (node (ref "IC1") (pin "36") (pinfunction "VDD_2_36") (pintype "power_in"))
      (node (ref "IC1") (pin "48") (pinfunction "VDD_3_48") (pintype "power_in"))
      (node (ref "IC1") (pin "9") (pinfunction "VDDA_9") (pintype "power_in"))
      (node (ref "IC2") (pin "2") (pinfunction "VOUT_2") (pintype "output"))
      (node (ref "IC2") (pin "4") (pinfunction "VOUT_4") (pintype "output"))
      (node (ref "IC5") (pin "3") (pinfunction "~{W}_3") (pintype "input"))
      (node (ref "IC5") (pin "7") (pinfunction "~{HOLD}_7") (pintype "input"))
      (node (ref "IC5") (pin "8") (pinfunction "VCC_8") (pintype "power_in"))
      (node (ref "R1") (pin "1") (pinfunction "1_1") (pintype "passive"))
      (node (ref "R2") (pin "1") (pinfunction "1_1") (pintype "passive"))
      (node (ref "R25") (pin "1") (pinfunction "1_1") (pintype "passive"))
      (node (ref "R4") (pin "1") (pinfunction "1_1") (pintype "passive"))
      (node (ref "R7") (pin "2") (pinfunction "2_2") (pintype "passive"))
      (node (ref "SD1") (pin "4") (pinfunction "VDD_4") (pintype "power_in"))
      (node (ref "T1") (pin "2") (pinfunction "E_2") (pintype "passive"))
      (node (ref "U1") (pin "P$1") (pinfunction "OEN_P$1") (pintype "bidirectional"))
      (node (ref "U1") (pin "P$4") (pinfunction "VDD_P$4") (pintype "power_in"))
      (node (ref "U2") (pin "117") (pinfunction "VCCIO7_117") (pintype "power_in"))
      (node (ref "U2") (pin "122") (pinfunction "VCCIO7_122") (pintype "power_in"))
      (node (ref "U2") (pin "130") (pinfunction "VCCIO8_130") (pintype "power_in"))
      (node (ref "U2") (pin "139") (pinfunction "VCCIO8_139") (pintype "power_in"))
      (node (ref "U2") (pin "17") (pinfunction "VCCIO1_17") (pintype "power_in"))
      (node (ref "U2") (pin "26") (pinfunction "VCCIO2_26") (pintype "power_in"))
      (node (ref "U2") (pin "40") (pinfunction "VCCIO3_40") (pintype "power_in"))
      (node (ref "U2") (pin "47") (pinfunction "VCCIO3_47") (pintype "power_in"))
      (node (ref "U2") (pin "56") (pinfunction "VCCIO4_56") (pintype "power_in"))
      (node (ref "U2") (pin "62") (pinfunction "VCCIO4_62") (pintype "power_in"))
      (node (ref "U2") (pin "81") (pinfunction "VCCIO5_81") (pintype "power_in"))
      (node (ref "U2") (pin "93") (pinfunction "VCCIO6_93") (pintype "power_in"))
    )
    (net (code "3") (name "2V5") (class "Default")
      (node (ref "C13") (pin "1") (pinfunction "1_1") (pintype "passive"))
      (node (ref "C14") (pin "1") (pinfunction "1_1") (pintype "passive"))
      (node (ref "C36") (pin "+") (pinfunction "+_+") (pintype "passive"))
      (node (ref "C37") (pin "2") (pinfunction "2_2") (pintype "passive"))
      (node (ref "IC3") (pin "2") (pinfunction "VOUT_2") (pintype "output"))
      (node (ref "IC3") (pin "4") (pinfunction "VOUT_4") (pintype "output"))
      (node (ref "IC4") (pin "3") (pinfunction "VIN_3") (pintype "input"))
      (node (ref "U2") (pin "107") (pinfunction "VCCA2_107") (pintype "power_in"))
      (node (ref "U2") (pin "35") (pinfunction "VCCA1_35") (pintype "power_in"))
    )
    (net (code "4") (name "5V") (class "Default")
      (node (ref "F1") (pin "1") (pinfunction "1_1") (pintype "passive"))
      (node (ref "U3") (pin "4") (pinfunction "VCC_4") (pintype "bidirectional"))
      (node (ref "USB") (pin "VCC") (pinfunction "VCC_VCC") (pintype "bidirectional"))
    )
    (net (code "5") (name "GND") (class "Default")
      (node (ref "A0") (pin "C") (pinfunction "C_C") (pintype "passive"))
      (node (ref "A1") (pin "C") (pinfunction "C_C") (pintype "passive"))
      (node (ref "A2") (pin "C") (pinfunction "C_C") (pintype "passive"))
      (node (ref "A3") (pin "C") (pinfunction "C_C") (pintype "passive"))
      (node (ref "A4") (pin "C") (pinfunction "C_C") (pintype "passive"))
      (node (ref "A5") (pin "C") (pinfunction "C_C") (pintype "passive"))
      (node (ref "A6") (pin "C") (pinfunction "C_C") (pintype "passive"))
      (node (ref "A7") (pin "C") (pinfunction "C_C") (pintype "passive"))
      (node (ref "B0") (pin "C") (pinfunction "C_C") (pintype "passive"))
      (node (ref "B1") (pin "C") (pinfunction "C_C") (pintype "passive"))
      (node (ref "B2") (pin "C") (pinfunction "C_C") (pintype "passive"))
      (node (ref "B3") (pin "C") (pinfunction "C_C") (pintype "passive"))
      (node (ref "B4") (pin "C") (pinfunction "C_C") (pintype "passive"))
      (node (ref "B5") (pin "C") (pinfunction "C_C") (pintype "passive"))
      (node (ref "B6") (pin "C") (pinfunction "C_C") (pintype "passive"))
      (node (ref "B7") (pin "C") (pinfunction "C_C") (pintype "passive"))
      (node (ref "C0_") (pin "C") (pinfunction "C_C") (pintype "passive"))
      (node (ref "C1") (pin "2") (pinfunction "2_2") (pintype "passive"))
      (node (ref "C10") (pin "2") (pinfunction "2_2") (pintype "passive"))
      (node (ref "C11") (pin "2") (pinfunction "2_2") (pintype "passive"))
      (node (ref "C12") (pin "2") (pinfunction "2_2") (pintype "passive"))
      (node (ref "C13") (pin "2") (pinfunction "2_2") (pintype "passive"))
      (node (ref "C14") (pin "2") (pinfunction "2_2") (pintype "passive"))
      (node (ref "C15") (pin "1") (pinfunction "1_1") (pintype "passive"))
      (node (ref "C16") (pin "2") (pinfunction "2_2") (pintype "passive"))
      (node (ref "C17") (pin "2") (pinfunction "2_2") (pintype "passive"))
      (node (ref "C18") (pin "2") (pinfunction "2_2") (pintype "passive"))
      (node (ref "C19") (pin "2") (pinfunction "2_2") (pintype "passive"))
      (node (ref "C1_") (pin "C") (pinfunction "C_C") (pintype "passive"))
      (node (ref "C2") (pin "2") (pinfunction "2_2") (pintype "passive"))
      (node (ref "C20") (pin "2") (pinfunction "2_2") (pintype "passive"))
      (node (ref "C21") (pin "2") (pinfunction "2_2") (pintype "passive"))
      (node (ref "C22") (pin "2") (pinfunction "2_2") (pintype "passive"))
      (node (ref "C23") (pin "2") (pinfunction "2_2") (pintype "passive"))
      (node (ref "C24") (pin "2") (pinfunction "2_2") (pintype "passive"))
      (node (ref "C25") (pin "2") (pinfunction "2_2") (pintype "passive"))
      (node (ref "C26") (pin "1") (pinfunction "1_1") (pintype "passive"))
      (node (ref "C27") (pin "1") (pinfunction "1_1") (pintype "passive"))
      (node (ref "C28") (pin "1") (pinfunction "1_1") (pintype "passive"))
      (node (ref "C29") (pin "1") (pinfunction "1_1") (pintype "passive"))
      (node (ref "C2_") (pin "C") (pinfunction "C_C") (pintype "passive"))
      (node (ref "C3") (pin "2") (pinfunction "2_2") (pintype "passive"))
      (node (ref "C30") (pin "2") (pinfunction "2_2") (pintype "passive"))
      (node (ref "C31") (pin "2") (pinfunction "2_2") (pintype "passive"))
      (node (ref "C32") (pin "2") (pinfunction "2_2") (pintype "passive"))
      (node (ref "C33") (pin "1") (pinfunction "1_1") (pintype "passive"))
      (node (ref "C34") (pin "-") (pinfunction "-_-") (pintype "passive"))
      (node (ref "C35") (pin "1") (pinfunction "1_1") (pintype "passive"))
      (node (ref "C36") (pin "-") (pinfunction "-_-") (pintype "passive"))
      (node (ref "C37") (pin "1") (pinfunction "1_1") (pintype "passive"))
      (node (ref "C38") (pin "-") (pinfunction "-_-") (pintype "passive"))
      (node (ref "C39") (pin "1") (pinfunction "1_1") (pintype "passive"))
      (node (ref "C3_") (pin "C") (pinfunction "C_C") (pintype "passive"))
      (node (ref "C4") (pin "2") (pinfunction "2_2") (pintype "passive"))
      (node (ref "C40") (pin "1") (pinfunction "1_1") (pintype "passive"))
      (node (ref "C4_") (pin "C") (pinfunction "C_C") (pintype "passive"))
      (node (ref "C5") (pin "2") (pinfunction "2_2") (pintype "passive"))
      (node (ref "C5_") (pin "C") (pinfunction "C_C") (pintype "passive"))
      (node (ref "C6") (pin "2") (pinfunction "2_2") (pintype "passive"))
      (node (ref "C6_") (pin "C") (pinfunction "C_C") (pintype "passive"))
      (node (ref "C7") (pin "2") (pinfunction "2_2") (pintype "passive"))
      (node (ref "C7_") (pin "C") (pinfunction "C_C") (pintype "passive"))
      (node (ref "C8") (pin "2") (pinfunction "2_2") (pintype "passive"))
      (node (ref "C9") (pin "2") (pinfunction "2_2") (pintype "passive"))
      (node (ref "CN1") (pin "5") (pinfunction "5_5") (pintype "bidirectional"))
      (node (ref "D-LED") (pin "C") (pinfunction "C_C") (pintype "passive"))
      (node (ref "HD1") (pin "39") (pinfunction "39_39") (pintype "passive"))
      (node (ref "HD1") (pin "40") (pinfunction "40_40") (pintype "passive"))
      (node (ref "HD2") (pin "39") (pinfunction "39_39") (pintype "passive"))
      (node (ref "HD2") (pin "40") (pinfunction "40_40") (pintype "passive"))
      (node (ref "IC1") (pin "23") (pinfunction "VSS_1_23") (pintype "power_in"))
      (node (ref "IC1") (pin "35") (pinfunction "VSS_2_35") (pintype "power_in"))
      (node (ref "IC1") (pin "47") (pinfunction "VSS_3_47") (pintype "power_in"))
      (node (ref "IC1") (pin "8") (pinfunction "VSSA_8") (pintype "power_in"))
      (node (ref "IC2") (pin "1") (pinfunction "GND_1") (pintype "power_in"))
      (node (ref "IC3") (pin "1") (pinfunction "GND_1") (pintype "power_in"))
      (node (ref "IC4") (pin "1") (pinfunction "GND_1") (pintype "power_in"))
      (node (ref "IC5") (pin "4") (pinfunction "GND_4") (pintype "power_in"))
      (node (ref "R3") (pin "1") (pinfunction "1_1") (pintype "passive"))
      (node (ref "R5") (pin "1") (pinfunction "1_1") (pintype "bidirectional"))
      (node (ref "R5") (pin "2") (pinfunction "2_2") (pintype "bidirectional"))
      (node (ref "R5") (pin "3") (pinfunction "3_3") (pintype "bidirectional"))
      (node (ref "R5") (pin "4") (pinfunction "4_4") (pintype "bidirectional"))
      (node (ref "R6") (pin "1") (pinfunction "1_1") (pintype "passive"))
      (node (ref "RST") (pin "B") (pinfunction "S_B") (pintype "passive"))
      (node (ref "RST") (pin "B'") (pinfunction "S1_B'") (pintype "passive"))
      (node (ref "SD1") (pin "6") (pinfunction "VSS_6") (pintype "power_in"))
      (node (ref "U1") (pin "P$2") (pinfunction "GND_P$2") (pintype "power_in"))
      (node (ref "U2") (pin "108") (pinfunction "GNDA2_108") (pintype "power_in"))
      (node (ref "U2") (pin "118") (pinfunction "GND_118") (pintype "power_in"))
      (node (ref "U2") (pin "123") (pinfunction "GND_123") (pintype "power_in"))
      (node (ref "U2") (pin "131") (pinfunction "GND_131") (pintype "power_in"))
      (node (ref "U2") (pin "140") (pinfunction "GND_140") (pintype "power_in"))
      (node (ref "U2") (pin "145") (pinfunction "EXP_145") (pintype "power_in"))
      (node (ref "U2") (pin "19") (pinfunction "GND_19") (pintype "power_in"))
      (node (ref "U2") (pin "22") (pinfunction "GND_22") (pintype "power_in"))
      (node (ref "U2") (pin "27") (pinfunction "GND_27") (pintype "power_in"))
      (node (ref "U2") (pin "36") (pinfunction "GNDA1_36") (pintype "power_in"))
      (node (ref "U2") (pin "4") (pinfunction "GND_4") (pintype "power_in"))
      (node (ref "U2") (pin "41") (pinfunction "GND_41") (pintype "power_in"))
      (node (ref "U2") (pin "48") (pinfunction "GND_48") (pintype "power_in"))
      (node (ref "U2") (pin "57") (pinfunction "GND_57") (pintype "power_in"))
      (node (ref "U2") (pin "63") (pinfunction "GND_63") (pintype "power_in"))
      (node (ref "U2") (pin "79") (pinfunction "GND_79") (pintype "power_in"))
      (node (ref "U2") (pin "82") (pinfunction "GND_82") (pintype "power_in"))
      (node (ref "U2") (pin "95") (pinfunction "GND_95") (pintype "power_in"))
      (node (ref "U3") (pin "1") (pinfunction "GND_1") (pintype "bidirectional"))
      (node (ref "USB") (pin "DIPGND1") (pinfunction "GND_DIPGND1") (pintype "bidirectional"))
      (node (ref "USB") (pin "DIPGND2") (pinfunction "GND_DIPGND2") (pintype "bidirectional"))
      (node (ref "USB") (pin "DIPGND3") (pinfunction "GND_DIPGND3") (pintype "bidirectional"))
      (node (ref "USB") (pin "DIPGND4") (pinfunction "GND_DIPGND4") (pintype "bidirectional"))
      (node (ref "USB") (pin "GND") (pinfunction "GND_GND") (pintype "bidirectional"))
    )
    (net (code "6") (name "LEDA0") (class "Default")
      (node (ref "R11") (pin "8") (pinfunction "8_8") (pintype "bidirectional"))
      (node (ref "U2") (pin "110") (pinfunction "IO_110") (pintype "bidirectional"))
    )
    (net (code "7") (name "LEDA1") (class "Default")
      (node (ref "R11") (pin "7") (pinfunction "7_7") (pintype "bidirectional"))
      (node (ref "U2") (pin "111") (pinfunction "IO_111") (pintype "bidirectional"))
    )
    (net (code "8") (name "LEDA2") (class "Default")
      (node (ref "R11") (pin "6") (pinfunction "6_6") (pintype "bidirectional"))
      (node (ref "U2") (pin "112") (pinfunction "IO_112") (pintype "bidirectional"))
    )
    (net (code "9") (name "LEDA3") (class "Default")
      (node (ref "R11") (pin "5") (pinfunction "5_5") (pintype "bidirectional"))
      (node (ref "U2") (pin "113") (pinfunction "IO_113") (pintype "bidirectional"))
    )
    (net (code "10") (name "LEDA4") (class "Default")
      (node (ref "R12") (pin "8") (pinfunction "8_8") (pintype "bidirectional"))
      (node (ref "U2") (pin "114") (pinfunction "IO_114") (pintype "bidirectional"))
    )
    (net (code "11") (name "LEDA5") (class "Default")
      (node (ref "R12") (pin "7") (pinfunction "7_7") (pintype "bidirectional"))
      (node (ref "U2") (pin "115") (pinfunction "IO_115") (pintype "bidirectional"))
    )
    (net (code "12") (name "LEDA6") (class "Default")
      (node (ref "R12") (pin "6") (pinfunction "6_6") (pintype "bidirectional"))
      (node (ref "U2") (pin "119") (pinfunction "IO_119") (pintype "bidirectional"))
    )
    (net (code "13") (name "LEDA7") (class "Default")
      (node (ref "R12") (pin "5") (pinfunction "5_5") (pintype "bidirectional"))
      (node (ref "U2") (pin "120") (pinfunction "IO_120") (pintype "bidirectional"))
    )
    (net (code "14") (name "LEDB0") (class "Default")
      (node (ref "R13") (pin "8") (pinfunction "8_8") (pintype "bidirectional"))
      (node (ref "U2") (pin "121") (pinfunction "IO_121") (pintype "bidirectional"))
    )
    (net (code "15") (name "LEDB1") (class "Default")
      (node (ref "R13") (pin "7") (pinfunction "7_7") (pintype "bidirectional"))
      (node (ref "U2") (pin "124") (pinfunction "IO_124") (pintype "bidirectional"))
    )
    (net (code "16") (name "LEDB2") (class "Default")
      (node (ref "R13") (pin "6") (pinfunction "6_6") (pintype "bidirectional"))
      (node (ref "U2") (pin "125") (pinfunction "IO_125") (pintype "bidirectional"))
    )
    (net (code "17") (name "LEDB3") (class "Default")
      (node (ref "R13") (pin "5") (pinfunction "5_5") (pintype "bidirectional"))
      (node (ref "U2") (pin "126") (pinfunction "IO_126") (pintype "bidirectional"))
    )
    (net (code "18") (name "LEDB4") (class "Default")
      (node (ref "R14") (pin "8") (pinfunction "8_8") (pintype "bidirectional"))
      (node (ref "U2") (pin "127") (pinfunction "IO_127") (pintype "bidirectional"))
    )
    (net (code "19") (name "LEDB5") (class "Default")
      (node (ref "R14") (pin "7") (pinfunction "7_7") (pintype "bidirectional"))
      (node (ref "U2") (pin "128") (pinfunction "IO_128") (pintype "bidirectional"))
    )
    (net (code "20") (name "LEDB6") (class "Default")
      (node (ref "R14") (pin "6") (pinfunction "6_6") (pintype "bidirectional"))
      (node (ref "U2") (pin "129") (pinfunction "IO_129") (pintype "bidirectional"))
    )
    (net (code "21") (name "LEDB7") (class "Default")
      (node (ref "R14") (pin "5") (pinfunction "5_5") (pintype "bidirectional"))
      (node (ref "U2") (pin "132") (pinfunction "IO_132") (pintype "bidirectional"))
    )
    (net (code "22") (name "LEDC0") (class "Default")
      (node (ref "R15") (pin "8") (pinfunction "8_8") (pintype "bidirectional"))
      (node (ref "U2") (pin "133") (pinfunction "IO_133") (pintype "bidirectional"))
    )
    (net (code "23") (name "LEDC1") (class "Default")
      (node (ref "R15") (pin "7") (pinfunction "7_7") (pintype "bidirectional"))
      (node (ref "U2") (pin "135") (pinfunction "IO_135") (pintype "bidirectional"))
    )
    (net (code "24") (name "LEDC2") (class "Default")
      (node (ref "R15") (pin "6") (pinfunction "6_6") (pintype "bidirectional"))
      (node (ref "U2") (pin "136") (pinfunction "IO_136") (pintype "bidirectional"))
    )
    (net (code "25") (name "LEDC3") (class "Default")
      (node (ref "R15") (pin "5") (pinfunction "5_5") (pintype "bidirectional"))
      (node (ref "U2") (pin "137") (pinfunction "IO_137") (pintype "bidirectional"))
    )
    (net (code "26") (name "LEDC4") (class "Default")
      (node (ref "R16") (pin "8") (pinfunction "8_8") (pintype "bidirectional"))
      (node (ref "U2") (pin "138") (pinfunction "IO_138") (pintype "bidirectional"))
    )
    (net (code "27") (name "LEDC5") (class "Default")
      (node (ref "R16") (pin "7") (pinfunction "7_7") (pintype "bidirectional"))
      (node (ref "U2") (pin "141") (pinfunction "IO_141") (pintype "bidirectional"))
    )
    (net (code "28") (name "LEDC6") (class "Default")
      (node (ref "R16") (pin "6") (pinfunction "6_6") (pintype "bidirectional"))
      (node (ref "U2") (pin "142") (pinfunction "IO_142") (pintype "bidirectional"))
    )
    (net (code "29") (name "LEDC7") (class "Default")
      (node (ref "R16") (pin "5") (pinfunction "5_5") (pintype "bidirectional"))
      (node (ref "U2") (pin "143") (pinfunction "IO_143") (pintype "bidirectional"))
    )
    (net (code "30") (name "LEDD") (class "Default")
      (node (ref "R17") (pin "2") (pinfunction "2_2") (pintype "passive"))
      (node (ref "U2") (pin "144") (pinfunction "IO_144") (pintype "bidirectional"))
    )
    (net (code "31") (name "NCONFIG") (class "Default")
      (node (ref "R19") (pin "7") (pinfunction "7_7") (pintype "bidirectional"))
      (node (ref "R2") (pin "2") (pinfunction "2_2") (pintype "passive"))
      (node (ref "U2") (pin "14") (pinfunction "NCONFIG_14") (pintype "bidirectional"))
    )
    (net (code "32") (name "NIOS_RST") (class "Default")
      (node (ref "R21") (pin "8") (pinfunction "8_8") (pintype "bidirectional"))
      (node (ref "U2") (pin "24") (pinfunction "CLK2_24") (pintype "bidirectional"))
    )
    (net (code "33") (name "Net-(A0-PadA)") (class "Default")
      (node (ref "A0") (pin "A") (pinfunction "A_A") (pintype "passive"))
      (node (ref "R11") (pin "1") (pinfunction "1_1") (pintype "bidirectional"))
    )
    (net (code "34") (name "Net-(A1-PadA)") (class "Default")
      (node (ref "A1") (pin "A") (pinfunction "A_A") (pintype "passive"))
      (node (ref "R11") (pin "2") (pinfunction "2_2") (pintype "bidirectional"))
    )
    (net (code "35") (name "Net-(A2-PadA)") (class "Default")
      (node (ref "A2") (pin "A") (pinfunction "A_A") (pintype "passive"))
      (node (ref "R11") (pin "3") (pinfunction "3_3") (pintype "bidirectional"))
    )
    (net (code "36") (name "Net-(A3-PadA)") (class "Default")
      (node (ref "A3") (pin "A") (pinfunction "A_A") (pintype "passive"))
      (node (ref "R11") (pin "4") (pinfunction "4_4") (pintype "bidirectional"))
    )
    (net (code "37") (name "Net-(A4-PadA)") (class "Default")
      (node (ref "A4") (pin "A") (pinfunction "A_A") (pintype "passive"))
      (node (ref "R12") (pin "1") (pinfunction "1_1") (pintype "bidirectional"))
    )
    (net (code "38") (name "Net-(A5-PadA)") (class "Default")
      (node (ref "A5") (pin "A") (pinfunction "A_A") (pintype "passive"))
      (node (ref "R12") (pin "2") (pinfunction "2_2") (pintype "bidirectional"))
    )
    (net (code "39") (name "Net-(A6-PadA)") (class "Default")
      (node (ref "A6") (pin "A") (pinfunction "A_A") (pintype "passive"))
      (node (ref "R12") (pin "3") (pinfunction "3_3") (pintype "bidirectional"))
    )
    (net (code "40") (name "Net-(A7-PadA)") (class "Default")
      (node (ref "A7") (pin "A") (pinfunction "A_A") (pintype "passive"))
      (node (ref "R12") (pin "4") (pinfunction "4_4") (pintype "bidirectional"))
    )
    (net (code "41") (name "Net-(B0-PadA)") (class "Default")
      (node (ref "B0") (pin "A") (pinfunction "A_A") (pintype "passive"))
      (node (ref "R13") (pin "1") (pinfunction "1_1") (pintype "bidirectional"))
    )
    (net (code "42") (name "Net-(B1-PadA)") (class "Default")
      (node (ref "B1") (pin "A") (pinfunction "A_A") (pintype "passive"))
      (node (ref "R13") (pin "2") (pinfunction "2_2") (pintype "bidirectional"))
    )
    (net (code "43") (name "Net-(B2-PadA)") (class "Default")
      (node (ref "B2") (pin "A") (pinfunction "A_A") (pintype "passive"))
      (node (ref "R13") (pin "3") (pinfunction "3_3") (pintype "bidirectional"))
    )
    (net (code "44") (name "Net-(B3-PadA)") (class "Default")
      (node (ref "B3") (pin "A") (pinfunction "A_A") (pintype "passive"))
      (node (ref "R13") (pin "4") (pinfunction "4_4") (pintype "bidirectional"))
    )
    (net (code "45") (name "Net-(B4-PadA)") (class "Default")
      (node (ref "B4") (pin "A") (pinfunction "A_A") (pintype "passive"))
      (node (ref "R14") (pin "1") (pinfunction "1_1") (pintype "bidirectional"))
    )
    (net (code "46") (name "Net-(B5-PadA)") (class "Default")
      (node (ref "B5") (pin "A") (pinfunction "A_A") (pintype "passive"))
      (node (ref "R14") (pin "2") (pinfunction "2_2") (pintype "bidirectional"))
    )
    (net (code "47") (name "Net-(B6-PadA)") (class "Default")
      (node (ref "B6") (pin "A") (pinfunction "A_A") (pintype "passive"))
      (node (ref "R14") (pin "3") (pinfunction "3_3") (pintype "bidirectional"))
    )
    (net (code "48") (name "Net-(B7-PadA)") (class "Default")
      (node (ref "B7") (pin "A") (pinfunction "A_A") (pintype "passive"))
      (node (ref "R14") (pin "4") (pinfunction "4_4") (pintype "bidirectional"))
    )
    (net (code "49") (name "Net-(C0_-PadA)") (class "Default")
      (node (ref "C0_") (pin "A") (pinfunction "A_A") (pintype "passive"))
      (node (ref "R15") (pin "1") (pinfunction "1_1") (pintype "bidirectional"))
    )
    (net (code "50") (name "Net-(C1_-PadA)") (class "Default")
      (node (ref "C1_") (pin "A") (pinfunction "A_A") (pintype "passive"))
      (node (ref "R15") (pin "2") (pinfunction "2_2") (pintype "bidirectional"))
    )
    (net (code "51") (name "Net-(C2_-PadA)") (class "Default")
      (node (ref "C2_") (pin "A") (pinfunction "A_A") (pintype "passive"))
      (node (ref "R15") (pin "3") (pinfunction "3_3") (pintype "bidirectional"))
    )
    (net (code "52") (name "Net-(C3_-PadA)") (class "Default")
      (node (ref "C3_") (pin "A") (pinfunction "A_A") (pintype "passive"))
      (node (ref "R15") (pin "4") (pinfunction "4_4") (pintype "bidirectional"))
    )
    (net (code "53") (name "Net-(C4_-PadA)") (class "Default")
      (node (ref "C4_") (pin "A") (pinfunction "A_A") (pintype "passive"))
      (node (ref "R16") (pin "1") (pinfunction "1_1") (pintype "bidirectional"))
    )
    (net (code "54") (name "Net-(C5_-PadA)") (class "Default")
      (node (ref "C5_") (pin "A") (pinfunction "A_A") (pintype "passive"))
      (node (ref "R16") (pin "2") (pinfunction "2_2") (pintype "bidirectional"))
    )
    (net (code "55") (name "Net-(C6_-PadA)") (class "Default")
      (node (ref "C6_") (pin "A") (pinfunction "A_A") (pintype "passive"))
      (node (ref "R16") (pin "3") (pinfunction "3_3") (pintype "bidirectional"))
    )
    (net (code "56") (name "Net-(C7_-PadA)") (class "Default")
      (node (ref "C7_") (pin "A") (pinfunction "A_A") (pintype "passive"))
      (node (ref "R16") (pin "4") (pinfunction "4_4") (pintype "bidirectional"))
    )
    (net (code "57") (name "Net-(D-LED-PadA)") (class "Default")
      (node (ref "D-LED") (pin "A") (pinfunction "A_A") (pintype "passive"))
      (node (ref "R17") (pin "1") (pinfunction "1_1") (pintype "passive"))
      (node (ref "R18") (pin "1") (pinfunction "1_1") (pintype "passive"))
    )
    (net (code "58") (name "Net-(D1-PadA)") (class "Default")
      (node (ref "D1") (pin "A") (pinfunction "A_A") (pintype "passive"))
      (node (ref "F1") (pin "2") (pinfunction "2_2") (pintype "passive"))
    )
    (net (code "59") (name "Net-(IC1D-PB8)") (class "Default")
      (node (ref "IC1") (pin "44") (pinfunction "BOOT0_44") (pintype "input"))
      (node (ref "IC1") (pin "45") (pinfunction "PB8_45") (pintype "bidirectional"))
      (node (ref "R6") (pin "2") (pinfunction "2_2") (pintype "passive"))
    )
    (net (code "60") (name "Net-(IC1G-PD0{slash}OSC<=)") (class "Default")
      (node (ref "C28") (pin "2") (pinfunction "2_2") (pintype "passive"))
      (node (ref "IC1") (pin "5") (pinfunction "PD0/OSC<=_5") (pintype "bidirectional"))
      (node (ref "X1") (pin "P$1") (pinfunction "P$1_P$1") (pintype "passive"))
    )
    (net (code "61") (name "Net-(IC1G-PD1{slash}OSC=>)") (class "Default")
      (node (ref "C27") (pin "2") (pinfunction "2_2") (pintype "passive"))
      (node (ref "IC1") (pin "6") (pinfunction "PD1/OSC=>_6") (pintype "bidirectional"))
      (node (ref "X1") (pin "P$2") (pinfunction "P$2_P$2") (pintype "passive"))
    )
    (net (code "62") (name "Net-(IC1I-NRST)") (class "Default")
      (node (ref "CN1") (pin "4") (pinfunction "4_4") (pintype "bidirectional"))
      (node (ref "IC1") (pin "7") (pinfunction "NRST_7") (pintype "input"))
      (node (ref "R7") (pin "1") (pinfunction "1_1") (pintype "passive"))
      (node (ref "RST") (pin "A") (pinfunction "P_A") (pintype "passive"))
      (node (ref "RST") (pin "A'") (pinfunction "P1_A'") (pintype "passive"))
    )
    (net (code "63") (name "Net-(IC2-VIN)") (class "Default")
      (node (ref "C33") (pin "2") (pinfunction "2_2") (pintype "passive"))
      (node (ref "C35") (pin "2") (pinfunction "2_2") (pintype "passive"))
      (node (ref "D1") (pin "C") (pinfunction "C_C") (pintype "passive"))
      (node (ref "IC2") (pin "3") (pinfunction "VIN_3") (pintype "input"))
      (node (ref "IC3") (pin "3") (pinfunction "VIN_3") (pintype "input"))
    )
    (net (code "64") (name "Net-(R8-Pad1)") (class "Default")
      (node (ref "R8") (pin "1") (pinfunction "1_1") (pintype "passive"))
      (node (ref "USB") (pin "D-") (pinfunction "D-_D-") (pintype "bidirectional"))
    )
    (net (code "65") (name "Net-(R9-Pad1)") (class "Default")
      (node (ref "R9") (pin "1") (pinfunction "1_1") (pintype "passive"))
      (node (ref "USB") (pin "D+") (pinfunction "D+_D+") (pintype "bidirectional"))
    )
    (net (code "66") (name "Net-(R22-Pad7)") (class "Default")
      (node (ref "R22") (pin "7") (pinfunction "7_7") (pintype "bidirectional"))
      (node (ref "SJ1") (pin "2") (pinfunction "2_2") (pintype "passive"))
    )
    (net (code "67") (name "Net-(R22-Pad8)") (class "Default")
      (node (ref "R22") (pin "8") (pinfunction "8_8") (pintype "bidirectional"))
      (node (ref "SJ2") (pin "2") (pinfunction "2_2") (pintype "passive"))
    )
    (net (code "68") (name "Net-(SD1-DAT1)") (class "Default")
      (node (ref "R25") (pin "2") (pinfunction "2_2") (pintype "passive"))
      (node (ref "SD1") (pin "1") (pinfunction "DAT2_1") (pintype "bidirectional"))
      (node (ref "SD1") (pin "8") (pinfunction "DAT1_8") (pintype "bidirectional"))
    )
    (net (code "69") (name "Net-(T1-C)") (class "Default")
      (node (ref "R10") (pin "1") (pinfunction "1_1") (pintype "passive"))
      (node (ref "T1") (pin "3") (pinfunction "C_3") (pintype "passive"))
    )
    (net (code "70") (name "Net-(U1-OUT)") (class "Default")
      (node (ref "U1") (pin "P$3") (pinfunction "OUT_P$3") (pintype "output"))
      (node (ref "U2") (pin "23") (pinfunction "CLK1_23") (pintype "bidirectional"))
    )
    (net (code "71") (name "Net-(U2-CONF_DONE)") (class "Default")
      (node (ref "R4") (pin "2") (pinfunction "2_2") (pintype "passive"))
      (node (ref "U2") (pin "92") (pinfunction "CONF_DONE_92") (pintype "bidirectional"))
    )
    (net (code "72") (name "Net-(U2-MSEL0)") (class "Default")
      (node (ref "R5") (pin "7") (pinfunction "7_7") (pintype "bidirectional"))
      (node (ref "U2") (pin "94") (pinfunction "MSEL0_94") (pintype "bidirectional"))
    )
    (net (code "73") (name "Net-(U2-MSEL1)") (class "Default")
      (node (ref "R5") (pin "6") (pinfunction "6_6") (pintype "bidirectional"))
      (node (ref "U2") (pin "96") (pinfunction "MSEL1_96") (pintype "bidirectional"))
    )
    (net (code "74") (name "Net-(U2-MSEL2)") (class "Default")
      (node (ref "R5") (pin "5") (pinfunction "5_5") (pintype "bidirectional"))
      (node (ref "U2") (pin "97") (pinfunction "MSEL2_97") (pintype "bidirectional"))
    )
    (net (code "75") (name "Net-(U2-NCE)") (class "Default")
      (node (ref "R3") (pin "2") (pinfunction "2_2") (pintype "passive"))
      (node (ref "U2") (pin "21") (pinfunction "NCE_21") (pintype "bidirectional"))
    )
    (net (code "76") (name "Net-(U2-NSTATUS)") (class "Default")
      (node (ref "R1") (pin "2") (pinfunction "2_2") (pintype "passive"))
      (node (ref "U2") (pin "9") (pinfunction "NSTATUS_9") (pintype "bidirectional"))
    )
    (net (code "77") (name "P1") (class "Default")
      (node (ref "R19") (pin "8") (pinfunction "8_8") (pintype "bidirectional"))
      (node (ref "U2") (pin "1") (pinfunction "IO_1") (pintype "bidirectional"))
    )
    (net (code "78") (name "P2") (class "Default")
      (node (ref "R20") (pin "5") (pinfunction "5_5") (pintype "bidirectional"))
      (node (ref "U2") (pin "2") (pinfunction "IO_2") (pintype "bidirectional"))
    )
    (net (code "79") (name "P3") (class "Default")
      (node (ref "R20") (pin "6") (pinfunction "6_6") (pintype "bidirectional"))
      (node (ref "U2") (pin "3") (pinfunction "IO_3") (pintype "bidirectional"))
    )
    (net (code "80") (name "P6") (class "Default")
      (node (ref "R20") (pin "7") (pinfunction "7_7") (pintype "bidirectional"))
      (node (ref "U2") (pin "6") (pinfunction "IO_6") (pintype "bidirectional"))
    )
    (net (code "81") (name "P7") (class "Default")
      (node (ref "R20") (pin "8") (pinfunction "8_8") (pintype "bidirectional"))
      (node (ref "U2") (pin "7") (pinfunction "IO_7") (pintype "bidirectional"))
    )
    (net (code "82") (name "P8") (class "Default")
      (node (ref "R21") (pin "5") (pinfunction "5_5") (pintype "bidirectional"))
      (node (ref "U2") (pin "8") (pinfunction "IO_8") (pintype "bidirectional"))
    )
    (net (code "83") (name "P10") (class "Default")
      (node (ref "R21") (pin "6") (pinfunction "6_6") (pintype "bidirectional"))
      (node (ref "U2") (pin "10") (pinfunction "IO_10") (pintype "bidirectional"))
    )
    (net (code "84") (name "P11") (class "Default")
      (node (ref "R21") (pin "7") (pinfunction "7_7") (pintype "bidirectional"))
      (node (ref "U2") (pin "11") (pinfunction "IO_11") (pintype "bidirectional"))
    )
    (net (code "85") (name "P38") (class "Default")
      (node (ref "R22") (pin "5") (pinfunction "5_5") (pintype "bidirectional"))
      (node (ref "U2") (pin "38") (pinfunction "IO_38") (pintype "bidirectional"))
    )
    (net (code "86") (name "P39") (class "Default")
      (node (ref "R22") (pin "6") (pinfunction "6_6") (pintype "bidirectional"))
      (node (ref "U2") (pin "39") (pinfunction "IO_39") (pintype "bidirectional"))
    )
    (net (code "87") (name "P42") (class "Default")
      (node (ref "SJ1") (pin "1") (pinfunction "1_1") (pintype "passive"))
      (node (ref "U2") (pin "42") (pinfunction "IO_42") (pintype "bidirectional"))
    )
    (net (code "88") (name "P43") (class "Default")
      (node (ref "SJ2") (pin "1") (pinfunction "1_1") (pintype "passive"))
      (node (ref "U2") (pin "43") (pinfunction "IO_43") (pintype "bidirectional"))
    )
    (net (code "89") (name "P44") (class "Default")
      (node (ref "R23") (pin "5") (pinfunction "5_5") (pintype "bidirectional"))
      (node (ref "U2") (pin "44") (pinfunction "IO_44") (pintype "bidirectional"))
    )
    (net (code "90") (name "P46") (class "Default")
      (node (ref "R23") (pin "6") (pinfunction "6_6") (pintype "bidirectional"))
      (node (ref "U2") (pin "46") (pinfunction "IO_46") (pintype "bidirectional"))
    )
    (net (code "91") (name "P49") (class "Default")
      (node (ref "HD1") (pin "33") (pinfunction "33_33") (pintype "passive"))
      (node (ref "U2") (pin "49") (pinfunction "IO_49") (pintype "bidirectional"))
    )
    (net (code "92") (name "P50") (class "Default")
      (node (ref "HD1") (pin "34") (pinfunction "34_34") (pintype "passive"))
      (node (ref "U2") (pin "50") (pinfunction "IO_50") (pintype "bidirectional"))
    )
    (net (code "93") (name "P51") (class "Default")
      (node (ref "HD1") (pin "35") (pinfunction "35_35") (pintype "passive"))
      (node (ref "U2") (pin "51") (pinfunction "IO_51") (pintype "bidirectional"))
    )
    (net (code "94") (name "P52") (class "Default")
      (node (ref "HD1") (pin "36") (pinfunction "36_36") (pintype "passive"))
      (node (ref "U2") (pin "52") (pinfunction "IO_52") (pintype "bidirectional"))
    )
    (net (code "95") (name "P53") (class "Default")
      (node (ref "HD2") (pin "1") (pinfunction "1_1") (pintype "passive"))
      (node (ref "U2") (pin "53") (pinfunction "IO_53") (pintype "bidirectional"))
    )
    (net (code "96") (name "P54") (class "Default")
      (node (ref "HD2") (pin "2") (pinfunction "2_2") (pintype "passive"))
      (node (ref "U2") (pin "54") (pinfunction "IO_54") (pintype "bidirectional"))
    )
    (net (code "97") (name "P55") (class "Default")
      (node (ref "HD2") (pin "3") (pinfunction "3_3") (pintype "passive"))
      (node (ref "U2") (pin "55") (pinfunction "IO_55") (pintype "bidirectional"))
    )
    (net (code "98") (name "P58") (class "Default")
      (node (ref "HD2") (pin "4") (pinfunction "4_4") (pintype "passive"))
      (node (ref "U2") (pin "58") (pinfunction "IO_58") (pintype "bidirectional"))
    )
    (net (code "99") (name "P59") (class "Default")
      (node (ref "HD2") (pin "5") (pinfunction "5_5") (pintype "passive"))
      (node (ref "U2") (pin "59") (pinfunction "IO_59") (pintype "bidirectional"))
    )
    (net (code "100") (name "P60") (class "Default")
      (node (ref "HD2") (pin "6") (pinfunction "6_6") (pintype "passive"))
      (node (ref "U2") (pin "60") (pinfunction "IO_60") (pintype "bidirectional"))
    )
    (net (code "101") (name "P64") (class "Default")
      (node (ref "HD2") (pin "7") (pinfunction "7_7") (pintype "passive"))
      (node (ref "U2") (pin "64") (pinfunction "IO_64") (pintype "bidirectional"))
    )
    (net (code "102") (name "P65") (class "Default")
      (node (ref "HD2") (pin "8") (pinfunction "8_8") (pintype "passive"))
      (node (ref "U2") (pin "65") (pinfunction "IO_65") (pintype "bidirectional"))
    )
    (net (code "103") (name "P66") (class "Default")
      (node (ref "HD2") (pin "9") (pinfunction "9_9") (pintype "passive"))
      (node (ref "U2") (pin "66") (pinfunction "IO_66") (pintype "bidirectional"))
    )
    (net (code "104") (name "P67") (class "Default")
      (node (ref "HD2") (pin "10") (pinfunction "10_10") (pintype "passive"))
      (node (ref "U2") (pin "67") (pinfunction "IO_67") (pintype "bidirectional"))
    )
    (net (code "105") (name "P68") (class "Default")
      (node (ref "HD2") (pin "11") (pinfunction "11_11") (pintype "passive"))
      (node (ref "U2") (pin "68") (pinfunction "IO_68") (pintype "bidirectional"))
    )
    (net (code "106") (name "P69") (class "Default")
      (node (ref "HD2") (pin "12") (pinfunction "12_12") (pintype "passive"))
      (node (ref "U2") (pin "69") (pinfunction "IO_69") (pintype "bidirectional"))
    )
    (net (code "107") (name "P70") (class "Default")
      (node (ref "HD2") (pin "13") (pinfunction "13_13") (pintype "passive"))
      (node (ref "U2") (pin "70") (pinfunction "IO_70") (pintype "bidirectional"))
    )
    (net (code "108") (name "P71") (class "Default")
      (node (ref "HD2") (pin "14") (pinfunction "14_14") (pintype "passive"))
      (node (ref "U2") (pin "71") (pinfunction "IO_71") (pintype "bidirectional"))
    )
    (net (code "109") (name "P72") (class "Default")
      (node (ref "HD2") (pin "15") (pinfunction "15_15") (pintype "passive"))
      (node (ref "U2") (pin "72") (pinfunction "IO_72") (pintype "bidirectional"))
    )
    (net (code "110") (name "P73") (class "Default")
      (node (ref "HD2") (pin "16") (pinfunction "16_16") (pintype "passive"))
      (node (ref "U2") (pin "73") (pinfunction "IO_73") (pintype "bidirectional"))
    )
    (net (code "111") (name "P74") (class "Default")
      (node (ref "HD2") (pin "17") (pinfunction "17_17") (pintype "passive"))
      (node (ref "U2") (pin "74") (pinfunction "IO_74") (pintype "bidirectional"))
    )
    (net (code "112") (name "P75") (class "Default")
      (node (ref "HD2") (pin "18") (pinfunction "18_18") (pintype "passive"))
      (node (ref "U2") (pin "75") (pinfunction "IO_75") (pintype "bidirectional"))
    )
    (net (code "113") (name "P76") (class "Default")
      (node (ref "HD2") (pin "19") (pinfunction "19_19") (pintype "passive"))
      (node (ref "U2") (pin "76") (pinfunction "IO_76") (pintype "bidirectional"))
    )
    (net (code "114") (name "P77") (class "Default")
      (node (ref "HD2") (pin "20") (pinfunction "20_20") (pintype "passive"))
      (node (ref "U2") (pin "77") (pinfunction "IO_77") (pintype "bidirectional"))
    )
    (net (code "115") (name "P80") (class "Default")
      (node (ref "HD2") (pin "21") (pinfunction "21_21") (pintype "passive"))
      (node (ref "U2") (pin "80") (pinfunction "IO_80") (pintype "bidirectional"))
    )
    (net (code "116") (name "P83") (class "Default")
      (node (ref "HD2") (pin "22") (pinfunction "22_22") (pintype "passive"))
      (node (ref "U2") (pin "83") (pinfunction "IO_83") (pintype "bidirectional"))
    )
    (net (code "117") (name "P84") (class "Default")
      (node (ref "HD2") (pin "23") (pinfunction "23_23") (pintype "passive"))
      (node (ref "U2") (pin "84") (pinfunction "IO_84") (pintype "bidirectional"))
    )
    (net (code "118") (name "P85") (class "Default")
      (node (ref "HD2") (pin "24") (pinfunction "24_24") (pintype "passive"))
      (node (ref "U2") (pin "85") (pinfunction "IO_85") (pintype "bidirectional"))
    )
    (net (code "119") (name "P86") (class "Default")
      (node (ref "HD2") (pin "25") (pinfunction "25_25") (pintype "passive"))
      (node (ref "U2") (pin "86") (pinfunction "IO_86") (pintype "bidirectional"))
    )
    (net (code "120") (name "P87") (class "Default")
      (node (ref "HD2") (pin "26") (pinfunction "26_26") (pintype "passive"))
      (node (ref "U2") (pin "87") (pinfunction "IO_87") (pintype "bidirectional"))
    )
    (net (code "121") (name "P88") (class "Default")
      (node (ref "HD2") (pin "27") (pinfunction "27_27") (pintype "passive"))
      (node (ref "U2") (pin "88") (pinfunction "CLK7_88") (pintype "bidirectional"))
    )
    (net (code "122") (name "P89") (class "Default")
      (node (ref "HD2") (pin "28") (pinfunction "28_28") (pintype "passive"))
      (node (ref "U2") (pin "89") (pinfunction "CLK6_89") (pintype "bidirectional"))
    )
    (net (code "123") (name "P90") (class "Default")
      (node (ref "HD2") (pin "29") (pinfunction "29_29") (pintype "passive"))
      (node (ref "U2") (pin "90") (pinfunction "CLK5_90") (pintype "bidirectional"))
    )
    (net (code "124") (name "P91") (class "Default")
      (node (ref "HD2") (pin "30") (pinfunction "30_30") (pintype "passive"))
      (node (ref "U2") (pin "91") (pinfunction "CLK4_91") (pintype "bidirectional"))
    )
    (net (code "125") (name "P98") (class "Default")
      (node (ref "HD2") (pin "31") (pinfunction "31_31") (pintype "passive"))
      (node (ref "U2") (pin "98") (pinfunction "IO_98") (pintype "bidirectional"))
    )
    (net (code "126") (name "P99") (class "Default")
      (node (ref "HD2") (pin "32") (pinfunction "32_32") (pintype "passive"))
      (node (ref "U2") (pin "99") (pinfunction "IO_99") (pintype "bidirectional"))
    )
    (net (code "127") (name "P100") (class "Default")
      (node (ref "HD2") (pin "33") (pinfunction "33_33") (pintype "passive"))
      (node (ref "U2") (pin "100") (pinfunction "IO_100") (pintype "bidirectional"))
    )
    (net (code "128") (name "P101") (class "Default")
      (node (ref "HD2") (pin "34") (pinfunction "34_34") (pintype "passive"))
      (node (ref "U2") (pin "101") (pinfunction "IO_101") (pintype "bidirectional"))
    )
    (net (code "129") (name "P103") (class "Default")
      (node (ref "HD2") (pin "35") (pinfunction "35_35") (pintype "passive"))
      (node (ref "U2") (pin "103") (pinfunction "IO_103") (pintype "bidirectional"))
    )
    (net (code "130") (name "P104") (class "Default")
      (node (ref "HD2") (pin "36") (pinfunction "36_36") (pintype "passive"))
      (node (ref "U2") (pin "104") (pinfunction "IO_104") (pintype "bidirectional"))
    )
    (net (code "131") (name "P105") (class "Default")
      (node (ref "HD2") (pin "37") (pinfunction "37_37") (pintype "passive"))
      (node (ref "U2") (pin "105") (pinfunction "IO_105") (pintype "bidirectional"))
    )
    (net (code "132") (name "P106") (class "Default")
      (node (ref "U2") (pin "106") (pinfunction "IO_106") (pintype "bidirectional"))
    )
    (net (code "133") (name "PA0") (class "Default")
      (node (ref "HD1") (pin "12") (pinfunction "12_12") (pintype "passive"))
      (node (ref "IC1") (pin "10") (pinfunction "PA0_10") (pintype "bidirectional"))
    )
    (net (code "134") (name "PA1") (class "Default")
      (node (ref "HD1") (pin "11") (pinfunction "11_11") (pintype "passive"))
      (node (ref "IC1") (pin "11") (pinfunction "PA1_11") (pintype "bidirectional"))
    )
    (net (code "135") (name "PA2") (class "Default")
      (node (ref "HD1") (pin "10") (pinfunction "10_10") (pintype "passive"))
      (node (ref "IC1") (pin "12") (pinfunction "PA2_12") (pintype "bidirectional"))
    )
    (net (code "136") (name "PA3") (class "Default")
      (node (ref "HD1") (pin "9") (pinfunction "9_9") (pintype "passive"))
      (node (ref "IC1") (pin "13") (pinfunction "PA3_13") (pintype "bidirectional"))
    )
    (net (code "137") (name "PA4") (class "Default")
      (node (ref "HD1") (pin "8") (pinfunction "8_8") (pintype "passive"))
      (node (ref "IC1") (pin "14") (pinfunction "PA4_14") (pintype "bidirectional"))
    )
    (net (code "138") (name "PA5") (class "Default")
      (node (ref "HD1") (pin "7") (pinfunction "7_7") (pintype "passive"))
      (node (ref "IC1") (pin "15") (pinfunction "PA5_15") (pintype "bidirectional"))
    )
    (net (code "139") (name "PA6") (class "Default")
      (node (ref "HD1") (pin "6") (pinfunction "6_6") (pintype "passive"))
      (node (ref "IC1") (pin "16") (pinfunction "PA6_16") (pintype "bidirectional"))
    )
    (net (code "140") (name "PA7") (class "Default")
      (node (ref "HD1") (pin "5") (pinfunction "5_5") (pintype "passive"))
      (node (ref "IC1") (pin "17") (pinfunction "PA7_17") (pintype "bidirectional"))
    )
    (net (code "141") (name "PA8") (class "Default")
      (node (ref "HD1") (pin "28") (pinfunction "28_28") (pintype "passive"))
      (node (ref "IC1") (pin "29") (pinfunction "PA8_29") (pintype "bidirectional"))
      (node (ref "R23") (pin "2") (pinfunction "2_2") (pintype "bidirectional"))
    )
    (net (code "142") (name "PA9") (class "Default")
      (node (ref "HD1") (pin "27") (pinfunction "27_27") (pintype "passive"))
      (node (ref "IC1") (pin "30") (pinfunction "PA9_30") (pintype "bidirectional"))
      (node (ref "R23") (pin "3") (pinfunction "3_3") (pintype "bidirectional"))
    )
    (net (code "143") (name "PA10") (class "Default")
      (node (ref "HD1") (pin "26") (pinfunction "26_26") (pintype "passive"))
      (node (ref "IC1") (pin "31") (pinfunction "PA10_31") (pintype "bidirectional"))
      (node (ref "R23") (pin "4") (pinfunction "4_4") (pintype "bidirectional"))
    )
    (net (code "144") (name "PA11") (class "Default")
      (node (ref "HD1") (pin "25") (pinfunction "25_25") (pintype "passive"))
      (node (ref "IC1") (pin "32") (pinfunction "PA11_32") (pintype "bidirectional"))
      (node (ref "R22") (pin "1") (pinfunction "1_1") (pintype "bidirectional"))
      (node (ref "R8") (pin "2") (pinfunction "2_2") (pintype "passive"))
      (node (ref "U3") (pin "3") (pinfunction "IO2_3") (pintype "bidirectional"))
    )
    (net (code "145") (name "PA12") (class "Default")
      (node (ref "HD1") (pin "24") (pinfunction "24_24") (pintype "passive"))
      (node (ref "IC1") (pin "33") (pinfunction "PA12_33") (pintype "bidirectional"))
      (node (ref "R10") (pin "2") (pinfunction "2_2") (pintype "passive"))
      (node (ref "R22") (pin "2") (pinfunction "2_2") (pintype "bidirectional"))
      (node (ref "R9") (pin "2") (pinfunction "2_2") (pintype "passive"))
      (node (ref "U3") (pin "2") (pinfunction "IO1_2") (pintype "bidirectional"))
    )
    (net (code "146") (name "PA13") (class "Default")
      (node (ref "CN1") (pin "3") (pinfunction "3_3") (pintype "bidirectional"))
      (node (ref "HD1") (pin "23") (pinfunction "23_23") (pintype "passive"))
      (node (ref "IC1") (pin "34") (pinfunction "PA13_34") (pintype "bidirectional"))
      (node (ref "IC5") (pin "1") (pinfunction "~{S}_1") (pintype "input"))
      (node (ref "R22") (pin "3") (pinfunction "3_3") (pintype "bidirectional"))
    )
    (net (code "147") (name "PA14") (class "Default")
      (node (ref "CN1") (pin "2") (pinfunction "2_2") (pintype "bidirectional"))
      (node (ref "HD1") (pin "22") (pinfunction "22_22") (pintype "passive"))
      (node (ref "IC1") (pin "37") (pinfunction "PA14_37") (pintype "bidirectional"))
      (node (ref "R22") (pin "4") (pinfunction "4_4") (pintype "bidirectional"))
      (node (ref "SD1") (pin "2") (pinfunction "CD/DAT3(~{CS})_2") (pintype "bidirectional"))
    )
    (net (code "148") (name "PA15") (class "Default")
      (node (ref "HD1") (pin "21") (pinfunction "21_21") (pintype "passive"))
      (node (ref "IC1") (pin "38") (pinfunction "PA15_38") (pintype "bidirectional"))
      (node (ref "R21") (pin "1") (pinfunction "1_1") (pintype "bidirectional"))
    )
    (net (code "149") (name "PB0") (class "Default")
      (node (ref "HD1") (pin "4") (pinfunction "4_4") (pintype "passive"))
      (node (ref "IC1") (pin "18") (pinfunction "PB0_18") (pintype "bidirectional"))
    )
    (net (code "150") (name "PB1") (class "Default")
      (node (ref "IC1") (pin "19") (pinfunction "PB1_19") (pintype "bidirectional"))
      (node (ref "R18") (pin "2") (pinfunction "2_2") (pintype "passive"))
    )
    (net (code "151") (name "PB2") (class "Default")
      (node (ref "HD1") (pin "3") (pinfunction "3_3") (pintype "passive"))
      (node (ref "IC1") (pin "20") (pinfunction "PB2_20") (pintype "bidirectional"))
      (node (ref "R19") (pin "2") (pinfunction "2_2") (pintype "bidirectional"))
    )
    (net (code "152") (name "PB3") (class "Default")
      (node (ref "HD1") (pin "20") (pinfunction "20_20") (pintype "passive"))
      (node (ref "IC1") (pin "39") (pinfunction "PB3_39") (pintype "bidirectional"))
      (node (ref "R21") (pin "2") (pinfunction "2_2") (pintype "bidirectional"))
    )
    (net (code "153") (name "PB4") (class "Default")
      (node (ref "HD1") (pin "19") (pinfunction "19_19") (pintype "passive"))
      (node (ref "IC1") (pin "40") (pinfunction "PB4_40") (pintype "bidirectional"))
      (node (ref "R21") (pin "3") (pinfunction "3_3") (pintype "bidirectional"))
    )
    (net (code "154") (name "PB5") (class "Default")
      (node (ref "HD1") (pin "18") (pinfunction "18_18") (pintype "passive"))
      (node (ref "IC1") (pin "41") (pinfunction "PB5_41") (pintype "bidirectional"))
      (node (ref "R21") (pin "4") (pinfunction "4_4") (pintype "bidirectional"))
    )
    (net (code "155") (name "PB6") (class "Default")
      (node (ref "HD1") (pin "17") (pinfunction "17_17") (pintype "passive"))
      (node (ref "IC1") (pin "42") (pinfunction "PB6_42") (pintype "bidirectional"))
      (node (ref "R20") (pin "1") (pinfunction "1_1") (pintype "bidirectional"))
    )
    (net (code "156") (name "PB7") (class "Default")
      (node (ref "HD1") (pin "16") (pinfunction "16_16") (pintype "passive"))
      (node (ref "IC1") (pin "43") (pinfunction "PB7_43") (pintype "bidirectional"))
      (node (ref "R20") (pin "2") (pinfunction "2_2") (pintype "bidirectional"))
    )
    (net (code "157") (name "PB9") (class "Default")
      (node (ref "IC1") (pin "46") (pinfunction "PB9_46") (pintype "bidirectional"))
      (node (ref "T1") (pin "1") (pinfunction "INPUT_1") (pintype "passive"))
    )
    (net (code "158") (name "PB10") (class "Default")
      (node (ref "HD1") (pin "2") (pinfunction "2_2") (pintype "passive"))
      (node (ref "IC1") (pin "21") (pinfunction "PB10_21") (pintype "bidirectional"))
      (node (ref "R19") (pin "3") (pinfunction "3_3") (pintype "bidirectional"))
    )
    (net (code "159") (name "PB11") (class "Default")
      (node (ref "HD1") (pin "1") (pinfunction "1_1") (pintype "passive"))
      (node (ref "IC1") (pin "22") (pinfunction "PB11_22") (pintype "bidirectional"))
      (node (ref "R19") (pin "4") (pinfunction "4_4") (pintype "bidirectional"))
    )
    (net (code "160") (name "PB12") (class "Default")
      (node (ref "HD1") (pin "32") (pinfunction "32_32") (pintype "passive"))
      (node (ref "IC1") (pin "25") (pinfunction "PB12_25") (pintype "bidirectional"))
      (node (ref "R24") (pin "2") (pinfunction "2_2") (pintype "bidirectional"))
    )
    (net (code "161") (name "PB13") (class "Default")
      (node (ref "HD1") (pin "31") (pinfunction "31_31") (pintype "passive"))
      (node (ref "IC1") (pin "26") (pinfunction "PB13_26") (pintype "bidirectional"))
      (node (ref "IC5") (pin "6") (pinfunction "C_6") (pintype "input"))
      (node (ref "R24") (pin "3") (pinfunction "3_3") (pintype "bidirectional"))
      (node (ref "SD1") (pin "5") (pinfunction "CLK(SCLK)_5") (pintype "input"))
    )
    (net (code "162") (name "PB14") (class "Default")
      (node (ref "HD1") (pin "30") (pinfunction "30_30") (pintype "passive"))
      (node (ref "IC1") (pin "27") (pinfunction "PB14_27") (pintype "bidirectional"))
      (node (ref "IC5") (pin "2") (pinfunction "Q_2") (pintype "tri_state"))
      (node (ref "R24") (pin "4") (pinfunction "4_4") (pintype "bidirectional"))
      (node (ref "SD1") (pin "7") (pinfunction "DAT0(DO)_7") (pintype "bidirectional"))
    )
    (net (code "163") (name "PB15") (class "Default")
      (node (ref "HD1") (pin "29") (pinfunction "29_29") (pintype "passive"))
      (node (ref "IC1") (pin "28") (pinfunction "PB15_28") (pintype "bidirectional"))
      (node (ref "IC5") (pin "5") (pinfunction "D_5") (pintype "input"))
      (node (ref "R23") (pin "1") (pinfunction "1_1") (pintype "bidirectional"))
      (node (ref "SD1") (pin "3") (pinfunction "CMD(DI)_3") (pintype "bidirectional"))
    )
    (net (code "164") (name "PC13") (class "Default")
      (node (ref "HD1") (pin "15") (pinfunction "15_15") (pintype "passive"))
      (node (ref "IC1") (pin "2") (pinfunction "PC13_2") (pintype "bidirectional"))
      (node (ref "R20") (pin "3") (pinfunction "3_3") (pintype "bidirectional"))
    )
    (net (code "165") (name "PC14") (class "Default")
      (node (ref "HD1") (pin "14") (pinfunction "14_14") (pintype "passive"))
      (node (ref "IC1") (pin "3") (pinfunction "PC14_3") (pintype "bidirectional"))
      (node (ref "R20") (pin "4") (pinfunction "4_4") (pintype "bidirectional"))
    )
    (net (code "166") (name "PC15") (class "Default")
      (node (ref "HD1") (pin "13") (pinfunction "13_13") (pintype "passive"))
      (node (ref "IC1") (pin "4") (pinfunction "PC15_4") (pintype "bidirectional"))
      (node (ref "R19") (pin "1") (pinfunction "1_1") (pintype "bidirectional"))
    )
    (net (code "167") (name "P_CS") (class "Default")
      (node (ref "R24") (pin "7") (pinfunction "7_7") (pintype "bidirectional"))
      (node (ref "U2") (pin "32") (pinfunction "IO_32") (pintype "bidirectional"))
    )
    (net (code "168") (name "P_MISO") (class "Default")
      (node (ref "R24") (pin "5") (pinfunction "5_5") (pintype "bidirectional"))
      (node (ref "U2") (pin "30") (pinfunction "IO_30") (pintype "bidirectional"))
    )
    (net (code "169") (name "P_MOSI") (class "Default")
      (node (ref "R23") (pin "8") (pinfunction "8_8") (pintype "bidirectional"))
      (node (ref "U2") (pin "13") (pinfunction "IO_13") (pintype "bidirectional"))
      (node (ref "U2") (pin "28") (pinfunction "IO_28") (pintype "bidirectional"))
    )
    (net (code "170") (name "P_RX") (class "Default")
      (node (ref "R19") (pin "6") (pinfunction "6_6") (pintype "bidirectional"))
      (node (ref "U2") (pin "33") (pinfunction "IO_33") (pintype "bidirectional"))
    )
    (net (code "171") (name "P_SCL") (class "Default")
      (node (ref "R24") (pin "6") (pinfunction "6_6") (pintype "bidirectional"))
      (node (ref "U2") (pin "12") (pinfunction "DCLK_12") (pintype "bidirectional"))
      (node (ref "U2") (pin "31") (pinfunction "IO_31") (pintype "bidirectional"))
    )
    (net (code "172") (name "P_TX") (class "Default")
      (node (ref "R19") (pin "5") (pinfunction "5_5") (pintype "bidirectional"))
      (node (ref "U2") (pin "34") (pinfunction "IO_34") (pintype "bidirectional"))
    )
    (net (code "173") (name "RSTREQ") (class "Default")
      (node (ref "R23") (pin "7") (pinfunction "7_7") (pintype "bidirectional"))
      (node (ref "U2") (pin "25") (pinfunction "CLK3_25") (pintype "bidirectional"))
    )
    (net (code "174") (name "VBAT") (class "Default")
      (node (ref "IC1") (pin "1") (pinfunction "VBAT_1") (pintype "power_in"))
    )
    (net (code "175") (name "unconnected-(CN1-Pad6)") (class "Default")
      (node (ref "CN1") (pin "6") (pinfunction "6_6") (pintype "bidirectional"))
    )
    (net (code "176") (name "unconnected-(R5-Pad8)") (class "Default")
      (node (ref "R5") (pin "8") (pinfunction "8_8") (pintype "bidirectional"))
    )
    (net (code "177") (name "unconnected-(R24-Pad1)") (class "Default")
      (node (ref "R24") (pin "1") (pinfunction "1_1") (pintype "bidirectional"))
    )
    (net (code "178") (name "unconnected-(R24-Pad8)") (class "Default")
      (node (ref "R24") (pin "8") (pinfunction "8_8") (pintype "bidirectional"))
    )
    (net (code "179") (name "unconnected-(SD1-PadS1)") (class "Default")
      (node (ref "SD1") (pin "S1") (pinfunction "S1_S1") (pintype "passive"))
    )
    (net (code "180") (name "unconnected-(SD1-PadS2)") (class "Default")
      (node (ref "SD1") (pin "S2") (pinfunction "S2_S2") (pintype "passive"))
    )
    (net (code "181") (name "unconnected-(SD1-PadS3)") (class "Default")
      (node (ref "SD1") (pin "S3") (pinfunction "S3_S3") (pintype "passive"))
    )
    (net (code "182") (name "unconnected-(SD1-PadS4)") (class "Default")
      (node (ref "SD1") (pin "S4") (pinfunction "S4_S4") (pintype "passive"))
    )
    (net (code "183") (name "unconnected-(SD1-~{CARD}-Pad9)") (class "Default")
      (node (ref "SD1") (pin "9") (pinfunction "~{CARD}_9") (pintype "passive"))
    )
    (net (code "184") (name "unconnected-(U2-TCK-Pad16)") (class "Default")
      (node (ref "U2") (pin "16") (pinfunction "TCK_16") (pintype "bidirectional"))
    )
    (net (code "185") (name "unconnected-(U2-TDI-Pad15)") (class "Default")
      (node (ref "U2") (pin "15") (pinfunction "TDI_15") (pintype "bidirectional"))
    )
    (net (code "186") (name "unconnected-(U2-TDO-Pad20)") (class "Default")
      (node (ref "U2") (pin "20") (pinfunction "TDO_20") (pintype "bidirectional"))
    )
    (net (code "187") (name "unconnected-(U2-TMS-Pad18)") (class "Default")
      (node (ref "U2") (pin "18") (pinfunction "TMS_18") (pintype "bidirectional"))
    )
    (net (code "188") (name "unconnected-(USB-PadID)") (class "Default")
      (node (ref "USB") (pin "ID") (pinfunction "ID_ID") (pintype "bidirectional"))
    )
  )
)
